# xen_teensy_motherboard_8cv4pt_mki.net
KiCad netlist of a schematic drawn in EAGLE
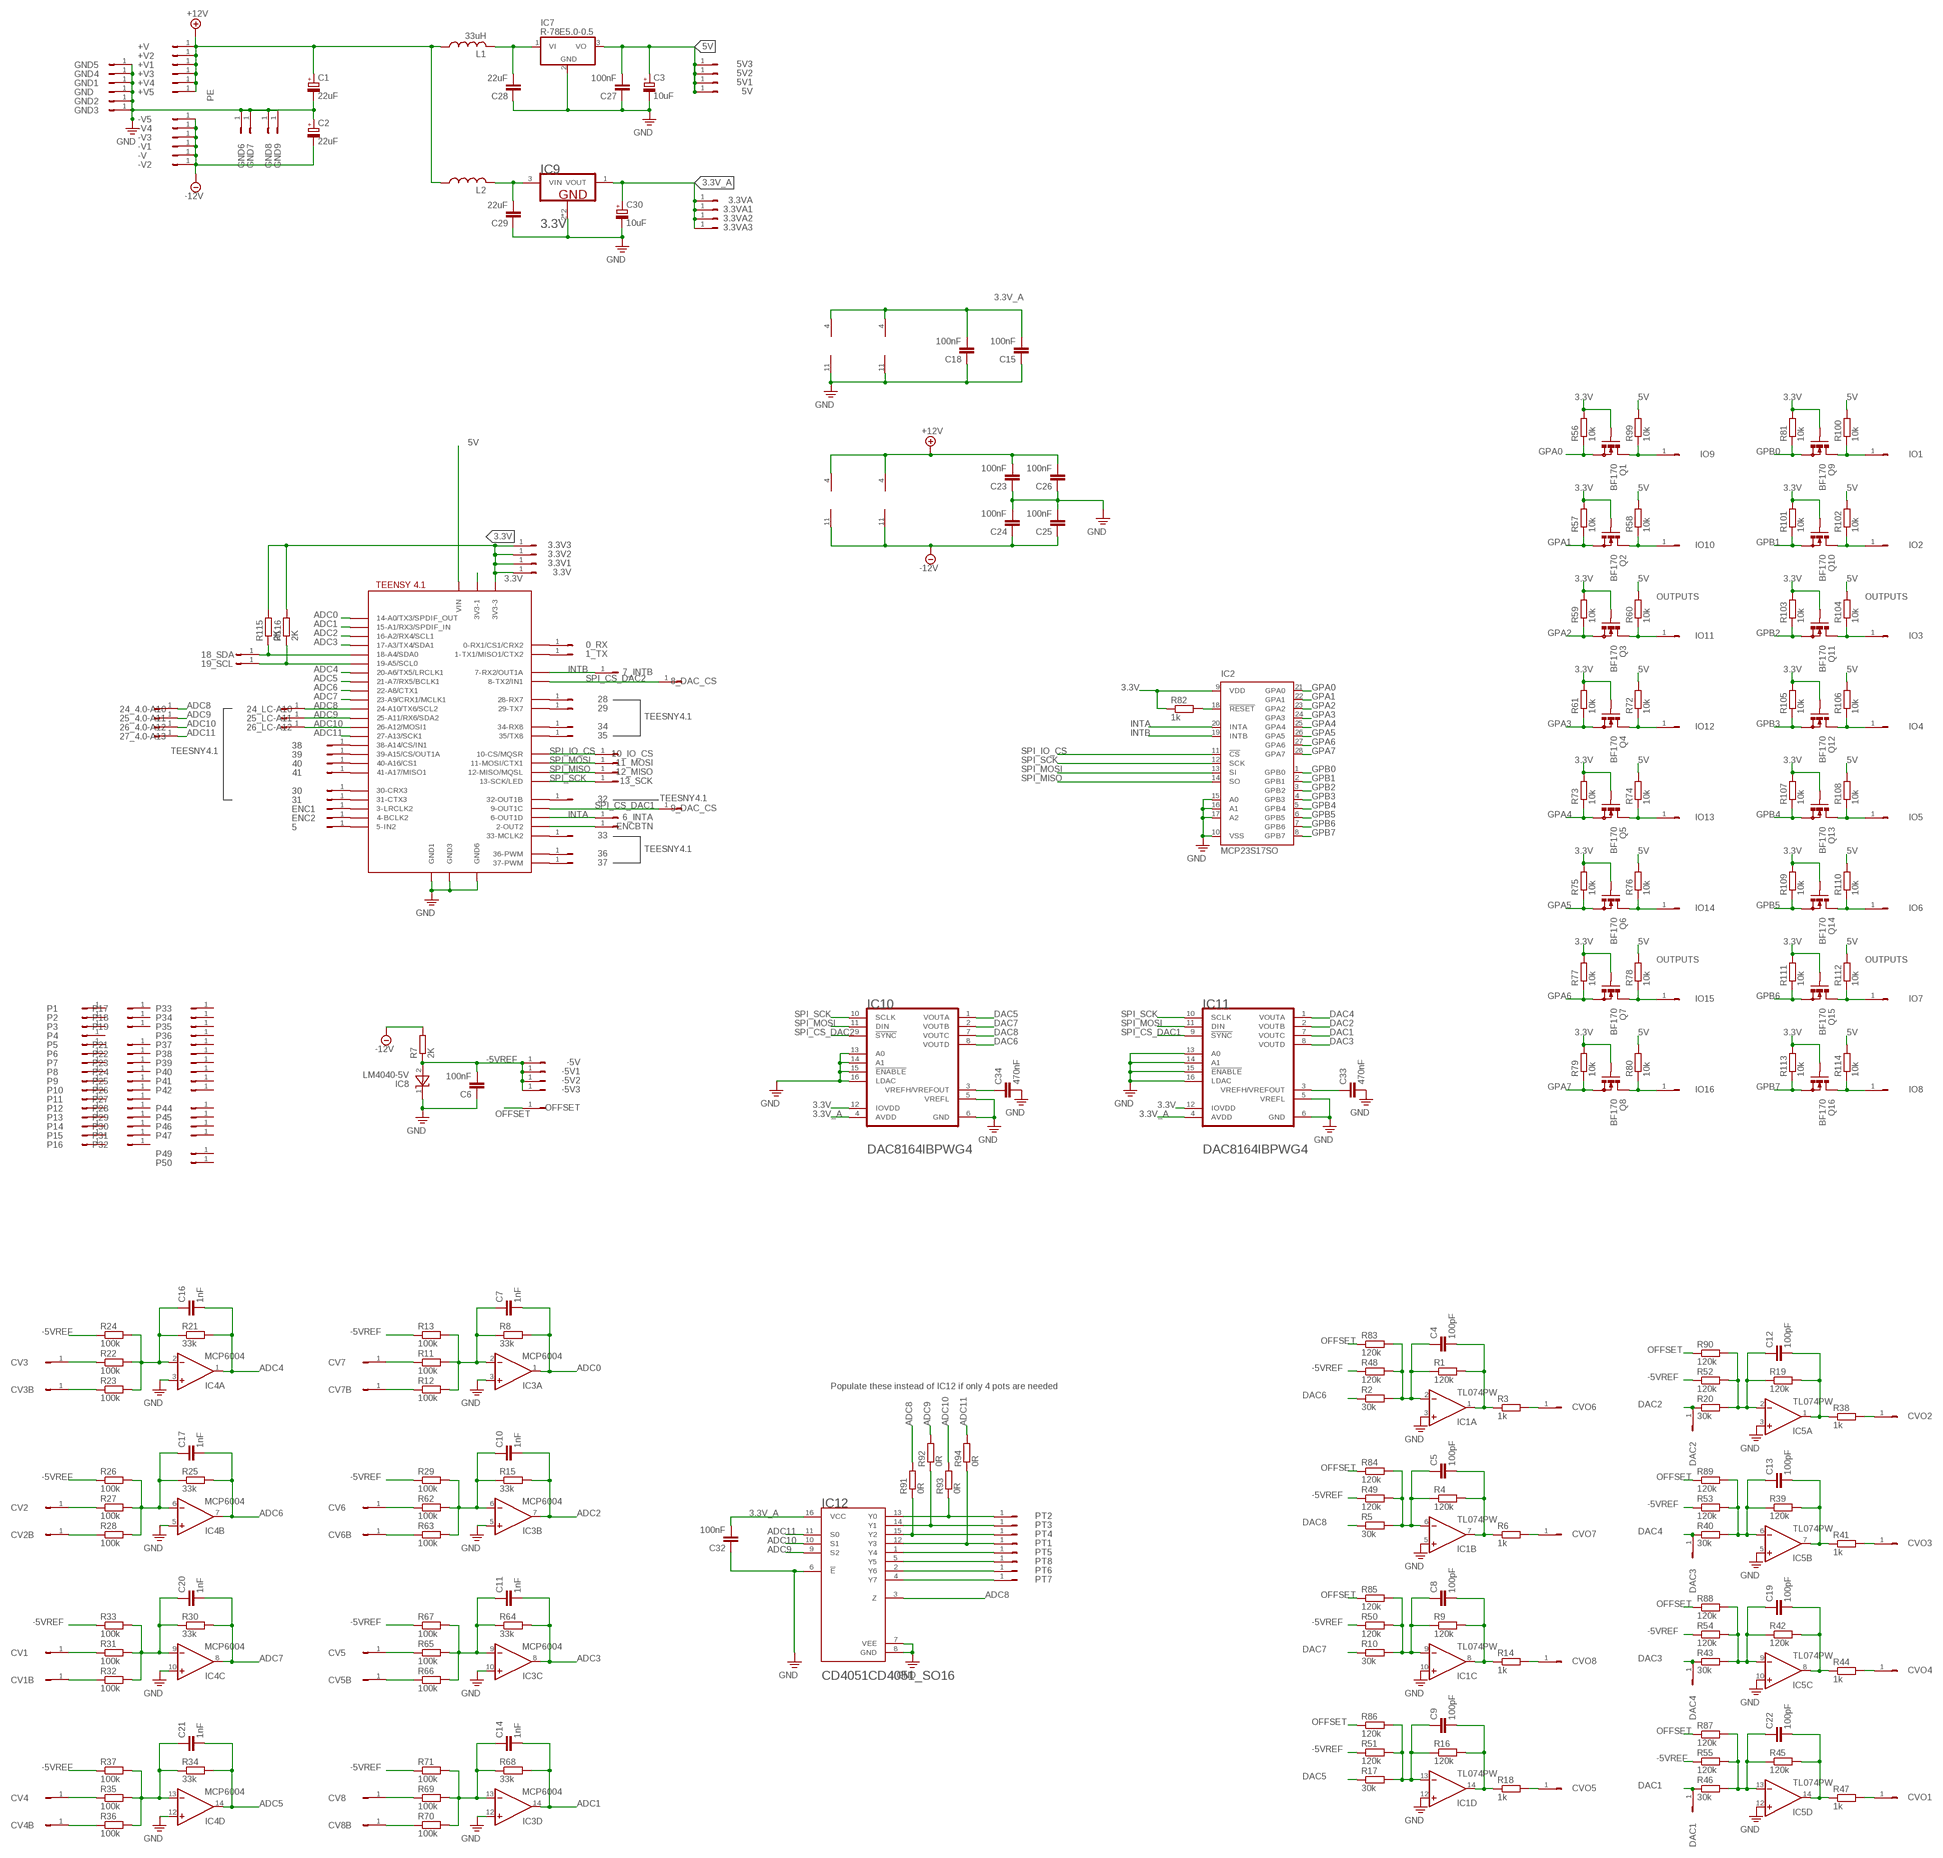
[diagram p0: schematic, sheet 1]

(export (version "E")
  (design (tool "Eeschema 10.0.6"))
  (components
    (comp (ref "+V")
      (value "HEADER/MALE/01")
      (footprint "eagle-import:HEADER_MALE_01")
      (fields (field (name "SPICEPREFIX") "X"))
      (libsource (lib "eagle-import") (part "HEADER/MALE/01"))
    )
    (comp (ref "+V1")
      (value "HEADER/MALE/01")
      (footprint "eagle-import:HEADER_MALE_01")
      (fields (field (name "SPICEPREFIX") "X"))
      (libsource (lib "eagle-import") (part "HEADER/MALE/01"))
    )
    (comp (ref "+V2")
      (value "HEADER/MALE/01")
      (footprint "eagle-import:HEADER_MALE_01")
      (fields (field (name "SPICEPREFIX") "X"))
      (libsource (lib "eagle-import") (part "HEADER/MALE/01"))
    )
    (comp (ref "+V3")
      (value "HEADER/MALE/01")
      (footprint "eagle-import:HEADER_MALE_01")
      (fields (field (name "SPICEPREFIX") "X"))
      (libsource (lib "eagle-import") (part "HEADER/MALE/01"))
    )
    (comp (ref "+V4")
      (value "HEADER/MALE/01")
      (footprint "eagle-import:HEADER_MALE_01")
      (fields (field (name "SPICEPREFIX") "X"))
      (libsource (lib "eagle-import") (part "HEADER/MALE/01"))
    )
    (comp (ref "+V5")
      (value "HEADER/MALE/01")
      (footprint "eagle-import:HEADER_MALE_01")
      (fields (field (name "SPICEPREFIX") "X"))
      (libsource (lib "eagle-import") (part "HEADER/MALE/01"))
    )
    (comp (ref "-5V")
      (value "HEADER/MALE/01")
      (footprint "eagle-import:HEADER_MALE_01")
      (fields (field (name "SPICEPREFIX") "X"))
      (libsource (lib "eagle-import") (part "HEADER/MALE/01"))
    )
    (comp (ref "-5V1")
      (value "HEADER/MALE/01")
      (footprint "eagle-import:HEADER_MALE_01")
      (fields (field (name "SPICEPREFIX") "X"))
      (libsource (lib "eagle-import") (part "HEADER/MALE/01"))
    )
    (comp (ref "-5V2")
      (value "HEADER/MALE/01")
      (footprint "eagle-import:HEADER_MALE_01")
      (fields (field (name "SPICEPREFIX") "X"))
      (libsource (lib "eagle-import") (part "HEADER/MALE/01"))
    )
    (comp (ref "-5V3")
      (value "HEADER/MALE/01")
      (footprint "eagle-import:HEADER_MALE_01")
      (fields (field (name "SPICEPREFIX") "X"))
      (libsource (lib "eagle-import") (part "HEADER/MALE/01"))
    )
    (comp (ref "-V")
      (value "HEADER/MALE/01")
      (footprint "eagle-import:HEADER_MALE_01")
      (fields (field (name "SPICEPREFIX") "X"))
      (libsource (lib "eagle-import") (part "HEADER/MALE/01"))
    )
    (comp (ref "-V1")
      (value "HEADER/MALE/01")
      (footprint "eagle-import:HEADER_MALE_01")
      (fields (field (name "SPICEPREFIX") "X"))
      (libsource (lib "eagle-import") (part "HEADER/MALE/01"))
    )
    (comp (ref "-V2")
      (value "HEADER/MALE/01")
      (footprint "eagle-import:HEADER_MALE_01")
      (fields (field (name "SPICEPREFIX") "X"))
      (libsource (lib "eagle-import") (part "HEADER/MALE/01"))
    )
    (comp (ref "-V3")
      (value "HEADER/MALE/01")
      (footprint "eagle-import:HEADER_MALE_01")
      (fields (field (name "SPICEPREFIX") "X"))
      (libsource (lib "eagle-import") (part "HEADER/MALE/01"))
    )
    (comp (ref "-V4")
      (value "HEADER/MALE/01")
      (footprint "eagle-import:HEADER_MALE_01")
      (fields (field (name "SPICEPREFIX") "X"))
      (libsource (lib "eagle-import") (part "HEADER/MALE/01"))
    )
    (comp (ref "-V5")
      (value "HEADER/MALE/01")
      (footprint "eagle-import:HEADER_MALE_01")
      (fields (field (name "SPICEPREFIX") "X"))
      (libsource (lib "eagle-import") (part "HEADER/MALE/01"))
    )
    (comp (ref "0_RX")
      (value "HEADER/MALE/01")
      (footprint "eagle-import:HEADER_MALE_01")
      (fields (field (name "SPICEPREFIX") "X"))
      (libsource (lib "eagle-import") (part "HEADER/MALE/01"))
    )
    (comp (ref "1_TX")
      (value "HEADER/MALE/01")
      (footprint "eagle-import:HEADER_MALE_01")
      (fields (field (name "SPICEPREFIX") "X"))
      (libsource (lib "eagle-import") (part "HEADER/MALE/01"))
    )
    (comp (ref "3.3V")
      (value "HEADER/MALE/01")
      (footprint "eagle-import:HEADER_MALE_01")
      (fields (field (name "SPICEPREFIX") "X"))
      (libsource (lib "eagle-import") (part "HEADER/MALE/01"))
    )
    (comp (ref "3.3V1")
      (value "HEADER/MALE/01")
      (footprint "eagle-import:HEADER_MALE_01")
      (fields (field (name "SPICEPREFIX") "X"))
      (libsource (lib "eagle-import") (part "HEADER/MALE/01"))
    )
    (comp (ref "3.3V2")
      (value "HEADER/MALE/01")
      (footprint "eagle-import:HEADER_MALE_01")
      (fields (field (name "SPICEPREFIX") "X"))
      (libsource (lib "eagle-import") (part "HEADER/MALE/01"))
    )
    (comp (ref "3.3V3")
      (value "HEADER/MALE/01")
      (footprint "eagle-import:HEADER_MALE_01")
      (fields (field (name "SPICEPREFIX") "X"))
      (libsource (lib "eagle-import") (part "HEADER/MALE/01"))
    )
    (comp (ref "3.3VA")
      (value "HEADER/MALE/01")
      (footprint "eagle-import:HEADER_MALE_01")
      (fields (field (name "SPICEPREFIX") "X"))
      (libsource (lib "eagle-import") (part "HEADER/MALE/01"))
    )
    (comp (ref "3.3VA1")
      (value "HEADER/MALE/01")
      (footprint "eagle-import:HEADER_MALE_01")
      (fields (field (name "SPICEPREFIX") "X"))
      (libsource (lib "eagle-import") (part "HEADER/MALE/01"))
    )
    (comp (ref "3.3VA2")
      (value "HEADER/MALE/01")
      (footprint "eagle-import:HEADER_MALE_01")
      (fields (field (name "SPICEPREFIX") "X"))
      (libsource (lib "eagle-import") (part "HEADER/MALE/01"))
    )
    (comp (ref "3.3VA3")
      (value "HEADER/MALE/01")
      (footprint "eagle-import:HEADER_MALE_01")
      (fields (field (name "SPICEPREFIX") "X"))
      (libsource (lib "eagle-import") (part "HEADER/MALE/01"))
    )
    (comp (ref "5")
      (value "HEADER/MALE/01")
      (footprint "eagle-import:HEADER_MALE_01")
      (fields (field (name "SPICEPREFIX") "X"))
      (libsource (lib "eagle-import") (part "HEADER/MALE/01"))
    )
    (comp (ref "5V")
      (value "HEADER/MALE/01")
      (footprint "eagle-import:HEADER_MALE_01")
      (fields (field (name "SPICEPREFIX") "X"))
      (libsource (lib "eagle-import") (part "HEADER/MALE/01"))
    )
    (comp (ref "5V1")
      (value "HEADER/MALE/01")
      (footprint "eagle-import:HEADER_MALE_01")
      (fields (field (name "SPICEPREFIX") "X"))
      (libsource (lib "eagle-import") (part "HEADER/MALE/01"))
    )
    (comp (ref "5V2")
      (value "HEADER/MALE/01")
      (footprint "eagle-import:HEADER_MALE_01")
      (fields (field (name "SPICEPREFIX") "X"))
      (libsource (lib "eagle-import") (part "HEADER/MALE/01"))
    )
    (comp (ref "5V3")
      (value "HEADER/MALE/01")
      (footprint "eagle-import:HEADER_MALE_01")
      (fields (field (name "SPICEPREFIX") "X"))
      (libsource (lib "eagle-import") (part "HEADER/MALE/01"))
    )
    (comp (ref "6_INTA")
      (value "HEADER/MALE/01")
      (footprint "eagle-import:HEADER_MALE_01")
      (fields (field (name "SPICEPREFIX") "X"))
      (libsource (lib "eagle-import") (part "HEADER/MALE/01"))
    )
    (comp (ref "7_INTB")
      (value "HEADER/MALE/01")
      (footprint "eagle-import:HEADER_MALE_01")
      (fields (field (name "SPICEPREFIX") "X"))
      (libsource (lib "eagle-import") (part "HEADER/MALE/01"))
    )
    (comp (ref "8_DAC_CS")
      (value "HEADER/MALE/01")
      (footprint "eagle-import:HEADER_MALE_01")
      (fields (field (name "SPICEPREFIX") "X"))
      (libsource (lib "eagle-import") (part "HEADER/MALE/01"))
    )
    (comp (ref "9_DAC_CS")
      (value "HEADER/MALE/01")
      (footprint "eagle-import:HEADER_MALE_01")
      (fields (field (name "SPICEPREFIX") "X"))
      (libsource (lib "eagle-import") (part "HEADER/MALE/01"))
    )
    (comp (ref "10_IO_CS")
      (value "HEADER/MALE/01")
      (footprint "eagle-import:HEADER_MALE_01")
      (fields (field (name "SPICEPREFIX") "X"))
      (libsource (lib "eagle-import") (part "HEADER/MALE/01"))
    )
    (comp (ref "11_MOSI")
      (value "HEADER/MALE/01")
      (footprint "eagle-import:HEADER_MALE_01")
      (fields (field (name "SPICEPREFIX") "X"))
      (libsource (lib "eagle-import") (part "HEADER/MALE/01"))
    )
    (comp (ref "12_MISO")
      (value "HEADER/MALE/01")
      (footprint "eagle-import:HEADER_MALE_01")
      (fields (field (name "SPICEPREFIX") "X"))
      (libsource (lib "eagle-import") (part "HEADER/MALE/01"))
    )
    (comp (ref "13_SCK")
      (value "HEADER/MALE/01")
      (footprint "eagle-import:HEADER_MALE_01")
      (fields (field (name "SPICEPREFIX") "X"))
      (libsource (lib "eagle-import") (part "HEADER/MALE/01"))
    )
    (comp (ref "18_SDA")
      (value "HEADER/MALE/01")
      (footprint "eagle-import:HEADER_MALE_01")
      (fields (field (name "SPICEPREFIX") "X"))
      (libsource (lib "eagle-import") (part "HEADER/MALE/01"))
    )
    (comp (ref "19_SCL")
      (value "HEADER/MALE/01")
      (footprint "eagle-import:HEADER_MALE_01")
      (fields (field (name "SPICEPREFIX") "X"))
      (libsource (lib "eagle-import") (part "HEADER/MALE/01"))
    )
    (comp (ref "24_4.0-A10")
      (value "HEADER/MALE/01")
      (footprint "eagle-import:HEADER_MALE_01")
      (fields (field (name "SPICEPREFIX") "X"))
      (libsource (lib "eagle-import") (part "HEADER/MALE/01"))
    )
    (comp (ref "24_LC-A10")
      (value "HEADER/MALE/01")
      (footprint "eagle-import:HEADER_MALE_01")
      (fields (field (name "SPICEPREFIX") "X"))
      (libsource (lib "eagle-import") (part "HEADER/MALE/01"))
    )
    (comp (ref "25_4.0-A11")
      (value "HEADER/MALE/01")
      (footprint "eagle-import:HEADER_MALE_01")
      (fields (field (name "SPICEPREFIX") "X"))
      (libsource (lib "eagle-import") (part "HEADER/MALE/01"))
    )
    (comp (ref "25_LC-A11")
      (value "HEADER/MALE/01")
      (footprint "eagle-import:HEADER_MALE_01")
      (fields (field (name "SPICEPREFIX") "X"))
      (libsource (lib "eagle-import") (part "HEADER/MALE/01"))
    )
    (comp (ref "26_4.0-A12")
      (value "HEADER/MALE/01")
      (footprint "eagle-import:HEADER_MALE_01")
      (fields (field (name "SPICEPREFIX") "X"))
      (libsource (lib "eagle-import") (part "HEADER/MALE/01"))
    )
    (comp (ref "26_LC-A12")
      (value "HEADER/MALE/01")
      (footprint "eagle-import:HEADER_MALE_01")
      (fields (field (name "SPICEPREFIX") "X"))
      (libsource (lib "eagle-import") (part "HEADER/MALE/01"))
    )
    (comp (ref "27_4.0-A13")
      (value "HEADER/MALE/01")
      (footprint "eagle-import:HEADER_MALE_01")
      (fields (field (name "SPICEPREFIX") "X"))
      (libsource (lib "eagle-import") (part "HEADER/MALE/01"))
    )
    (comp (ref "28")
      (value "HEADER/MALE/01")
      (footprint "eagle-import:HEADER_MALE_01")
      (fields (field (name "SPICEPREFIX") "X"))
      (libsource (lib "eagle-import") (part "HEADER/MALE/01"))
    )
    (comp (ref "29")
      (value "HEADER/MALE/01")
      (footprint "eagle-import:HEADER_MALE_01")
      (fields (field (name "SPICEPREFIX") "X"))
      (libsource (lib "eagle-import") (part "HEADER/MALE/01"))
    )
    (comp (ref "30")
      (value "HEADER/MALE/01")
      (footprint "eagle-import:HEADER_MALE_01")
      (fields (field (name "SPICEPREFIX") "X"))
      (libsource (lib "eagle-import") (part "HEADER/MALE/01"))
    )
    (comp (ref "31")
      (value "HEADER/MALE/01")
      (footprint "eagle-import:HEADER_MALE_01")
      (fields (field (name "SPICEPREFIX") "X"))
      (libsource (lib "eagle-import") (part "HEADER/MALE/01"))
    )
    (comp (ref "32")
      (value "HEADER/MALE/01")
      (footprint "eagle-import:HEADER_MALE_01")
      (fields (field (name "SPICEPREFIX") "X"))
      (libsource (lib "eagle-import") (part "HEADER/MALE/01"))
    )
    (comp (ref "33")
      (value "HEADER/MALE/01")
      (footprint "eagle-import:HEADER_MALE_01")
      (fields (field (name "SPICEPREFIX") "X"))
      (libsource (lib "eagle-import") (part "HEADER/MALE/01"))
    )
    (comp (ref "34")
      (value "HEADER/MALE/01")
      (footprint "eagle-import:HEADER_MALE_01")
      (fields (field (name "SPICEPREFIX") "X"))
      (libsource (lib "eagle-import") (part "HEADER/MALE/01"))
    )
    (comp (ref "35")
      (value "HEADER/MALE/01")
      (footprint "eagle-import:HEADER_MALE_01")
      (fields (field (name "SPICEPREFIX") "X"))
      (libsource (lib "eagle-import") (part "HEADER/MALE/01"))
    )
    (comp (ref "36")
      (value "HEADER/MALE/01")
      (footprint "eagle-import:HEADER_MALE_01")
      (fields (field (name "SPICEPREFIX") "X"))
      (libsource (lib "eagle-import") (part "HEADER/MALE/01"))
    )
    (comp (ref "37")
      (value "HEADER/MALE/01")
      (footprint "eagle-import:HEADER_MALE_01")
      (fields (field (name "SPICEPREFIX") "X"))
      (libsource (lib "eagle-import") (part "HEADER/MALE/01"))
    )
    (comp (ref "38")
      (value "HEADER/MALE/01")
      (footprint "eagle-import:HEADER_MALE_01")
      (fields (field (name "SPICEPREFIX") "X"))
      (libsource (lib "eagle-import") (part "HEADER/MALE/01"))
    )
    (comp (ref "39")
      (value "HEADER/MALE/01")
      (footprint "eagle-import:HEADER_MALE_01")
      (fields (field (name "SPICEPREFIX") "X"))
      (libsource (lib "eagle-import") (part "HEADER/MALE/01"))
    )
    (comp (ref "40")
      (value "HEADER/MALE/01")
      (footprint "eagle-import:HEADER_MALE_01")
      (fields (field (name "SPICEPREFIX") "X"))
      (libsource (lib "eagle-import") (part "HEADER/MALE/01"))
    )
    (comp (ref "41")
      (value "HEADER/MALE/01")
      (footprint "eagle-import:HEADER_MALE_01")
      (fields (field (name "SPICEPREFIX") "X"))
      (libsource (lib "eagle-import") (part "HEADER/MALE/01"))
    )
    (comp (ref "C1")
      (value "22uF")
      (footprint "eagle-import:SV-C")
      (fields (field (name "SPICEPREFIX") "C"))
      (libsource (lib "eagle-import") (part "CAPACITOR/POLARIZEDSMDC"))
    )
    (comp (ref "C2")
      (value "22uF")
      (footprint "eagle-import:SV-C")
      (fields (field (name "SPICEPREFIX") "C"))
      (libsource (lib "eagle-import") (part "CAPACITOR/POLARIZEDSMDC"))
    )
    (comp (ref "C3")
      (value "10uF")
      (footprint "eagle-import:SV-B")
      (fields (field (name "SPICEPREFIX") "C"))
      (libsource (lib "eagle-import") (part "CAPACITOR/POLARIZEDSMDB"))
    )
    (comp (ref "C4")
      (value "100pF")
      (footprint "eagle-import:C0603")
      (libsource (lib "eagle-import") (part "CAPACITORC0603"))
    )
    (comp (ref "C5")
      (value "100pF")
      (footprint "eagle-import:C0603")
      (libsource (lib "eagle-import") (part "CAPACITORC0603"))
    )
    (comp (ref "C6")
      (value "100nF")
      (footprint "eagle-import:C0603")
      (libsource (lib "eagle-import") (part "CAPACITORC0603"))
    )
    (comp (ref "C7")
      (value "1nF")
      (footprint "eagle-import:C0603")
      (libsource (lib "eagle-import") (part "CAPACITORC0603"))
    )
    (comp (ref "C8")
      (value "100pF")
      (footprint "eagle-import:C0603")
      (libsource (lib "eagle-import") (part "CAPACITORC0603"))
    )
    (comp (ref "C9")
      (value "100pF")
      (footprint "eagle-import:C0603")
      (libsource (lib "eagle-import") (part "CAPACITORC0603"))
    )
    (comp (ref "C10")
      (value "1nF")
      (footprint "eagle-import:C0603")
      (libsource (lib "eagle-import") (part "CAPACITORC0603"))
    )
    (comp (ref "C11")
      (value "1nF")
      (footprint "eagle-import:C0603")
      (libsource (lib "eagle-import") (part "CAPACITORC0603"))
    )
    (comp (ref "C12")
      (value "100pF")
      (footprint "eagle-import:C0603")
      (libsource (lib "eagle-import") (part "CAPACITORC0603"))
    )
    (comp (ref "C13")
      (value "100pF")
      (footprint "eagle-import:C0603")
      (libsource (lib "eagle-import") (part "CAPACITORC0603"))
    )
    (comp (ref "C14")
      (value "1nF")
      (footprint "eagle-import:C0603")
      (libsource (lib "eagle-import") (part "CAPACITORC0603"))
    )
    (comp (ref "C15")
      (value "100nF")
      (footprint "eagle-import:C0603")
      (libsource (lib "eagle-import") (part "CAPACITORC0603"))
    )
    (comp (ref "C16")
      (value "1nF")
      (footprint "eagle-import:C0603")
      (libsource (lib "eagle-import") (part "CAPACITORC0603"))
    )
    (comp (ref "C17")
      (value "1nF")
      (footprint "eagle-import:C0603")
      (libsource (lib "eagle-import") (part "CAPACITORC0603"))
    )
    (comp (ref "C18")
      (value "100nF")
      (footprint "eagle-import:C0603")
      (libsource (lib "eagle-import") (part "CAPACITORC0603"))
    )
    (comp (ref "C19")
      (value "100pF")
      (footprint "eagle-import:C0603")
      (libsource (lib "eagle-import") (part "CAPACITORC0603"))
    )
    (comp (ref "C20")
      (value "1nF")
      (footprint "eagle-import:C0603")
      (libsource (lib "eagle-import") (part "CAPACITORC0603"))
    )
    (comp (ref "C21")
      (value "1nF")
      (footprint "eagle-import:C0603")
      (libsource (lib "eagle-import") (part "CAPACITORC0603"))
    )
    (comp (ref "C22")
      (value "100pF")
      (footprint "eagle-import:C0603")
      (libsource (lib "eagle-import") (part "CAPACITORC0603"))
    )
    (comp (ref "C23")
      (value "100nF")
      (footprint "eagle-import:C0603")
      (libsource (lib "eagle-import") (part "CAPACITORC0603"))
    )
    (comp (ref "C24")
      (value "100nF")
      (footprint "eagle-import:C0603")
      (libsource (lib "eagle-import") (part "CAPACITORC0603"))
    )
    (comp (ref "C25")
      (value "100nF")
      (footprint "eagle-import:C0603")
      (libsource (lib "eagle-import") (part "CAPACITORC0603"))
    )
    (comp (ref "C26")
      (value "100nF")
      (footprint "eagle-import:C0603")
      (libsource (lib "eagle-import") (part "CAPACITORC0603"))
    )
    (comp (ref "C27")
      (value "100nF")
      (footprint "eagle-import:C0603")
      (libsource (lib "eagle-import") (part "CAPACITORC0603"))
    )
    (comp (ref "C28")
      (value "22uF")
      (footprint "eagle-import:C0805")
      (libsource (lib "eagle-import") (part "CAPACITORC0805"))
    )
    (comp (ref "C29")
      (value "22uF")
      (footprint "eagle-import:C0805")
      (libsource (lib "eagle-import") (part "CAPACITORC0805"))
    )
    (comp (ref "C30")
      (value "10uF")
      (footprint "eagle-import:SV-B")
      (fields (field (name "SPICEPREFIX") "C"))
      (libsource (lib "eagle-import") (part "CAPACITOR/POLARIZEDSMDB"))
    )
    (comp (ref "C32")
      (value "100nF")
      (footprint "eagle-import:C0603")
      (libsource (lib "eagle-import") (part "CAPACITORC0603"))
    )
    (comp (ref "C33")
      (value "470nF")
      (footprint "eagle-import:C0603")
      (libsource (lib "eagle-import") (part "CAPACITORC0603"))
    )
    (comp (ref "C34")
      (value "470nF")
      (footprint "eagle-import:C0603")
      (libsource (lib "eagle-import") (part "CAPACITORC0603"))
    )
    (comp (ref "CV1")
      (value "HEADER/MALE/01")
      (footprint "eagle-import:HEADER_MALE_01")
      (fields (field (name "SPICEPREFIX") "X"))
      (libsource (lib "eagle-import") (part "HEADER/MALE/01"))
    )
    (comp (ref "CV1B")
      (value "HEADER/MALE/01")
      (footprint "eagle-import:HEADER_MALE_01")
      (fields (field (name "SPICEPREFIX") "X"))
      (libsource (lib "eagle-import") (part "HEADER/MALE/01"))
    )
    (comp (ref "CV2")
      (value "HEADER/MALE/01")
      (footprint "eagle-import:HEADER_MALE_01")
      (fields (field (name "SPICEPREFIX") "X"))
      (libsource (lib "eagle-import") (part "HEADER/MALE/01"))
    )
    (comp (ref "CV2B")
      (value "HEADER/MALE/01")
      (footprint "eagle-import:HEADER_MALE_01")
      (fields (field (name "SPICEPREFIX") "X"))
      (libsource (lib "eagle-import") (part "HEADER/MALE/01"))
    )
    (comp (ref "CV3")
      (value "HEADER/MALE/01")
      (footprint "eagle-import:HEADER_MALE_01")
      (fields (field (name "SPICEPREFIX") "X"))
      (libsource (lib "eagle-import") (part "HEADER/MALE/01"))
    )
    (comp (ref "CV3B")
      (value "HEADER/MALE/01")
      (footprint "eagle-import:HEADER_MALE_01")
      (fields (field (name "SPICEPREFIX") "X"))
      (libsource (lib "eagle-import") (part "HEADER/MALE/01"))
    )
    (comp (ref "CV4")
      (value "HEADER/MALE/01")
      (footprint "eagle-import:HEADER_MALE_01")
      (fields (field (name "SPICEPREFIX") "X"))
      (libsource (lib "eagle-import") (part "HEADER/MALE/01"))
    )
    (comp (ref "CV4B")
      (value "HEADER/MALE/01")
      (footprint "eagle-import:HEADER_MALE_01")
      (fields (field (name "SPICEPREFIX") "X"))
      (libsource (lib "eagle-import") (part "HEADER/MALE/01"))
    )
    (comp (ref "CV5")
      (value "HEADER/MALE/01")
      (footprint "eagle-import:HEADER_MALE_01")
      (fields (field (name "SPICEPREFIX") "X"))
      (libsource (lib "eagle-import") (part "HEADER/MALE/01"))
    )
    (comp (ref "CV5B")
      (value "HEADER/MALE/01")
      (footprint "eagle-import:HEADER_MALE_01")
      (fields (field (name "SPICEPREFIX") "X"))
      (libsource (lib "eagle-import") (part "HEADER/MALE/01"))
    )
    (comp (ref "CV6")
      (value "HEADER/MALE/01")
      (footprint "eagle-import:HEADER_MALE_01")
      (fields (field (name "SPICEPREFIX") "X"))
      (libsource (lib "eagle-import") (part "HEADER/MALE/01"))
    )
    (comp (ref "CV6B")
      (value "HEADER/MALE/01")
      (footprint "eagle-import:HEADER_MALE_01")
      (fields (field (name "SPICEPREFIX") "X"))
      (libsource (lib "eagle-import") (part "HEADER/MALE/01"))
    )
    (comp (ref "CV7")
      (value "HEADER/MALE/01")
      (footprint "eagle-import:HEADER_MALE_01")
      (fields (field (name "SPICEPREFIX") "X"))
      (libsource (lib "eagle-import") (part "HEADER/MALE/01"))
    )
    (comp (ref "CV7B")
      (value "HEADER/MALE/01")
      (footprint "eagle-import:HEADER_MALE_01")
      (fields (field (name "SPICEPREFIX") "X"))
      (libsource (lib "eagle-import") (part "HEADER/MALE/01"))
    )
    (comp (ref "CV8")
      (value "HEADER/MALE/01")
      (footprint "eagle-import:HEADER_MALE_01")
      (fields (field (name "SPICEPREFIX") "X"))
      (libsource (lib "eagle-import") (part "HEADER/MALE/01"))
    )
    (comp (ref "CV8B")
      (value "HEADER/MALE/01")
      (footprint "eagle-import:HEADER_MALE_01")
      (fields (field (name "SPICEPREFIX") "X"))
      (libsource (lib "eagle-import") (part "HEADER/MALE/01"))
    )
    (comp (ref "CVO1")
      (value "HEADER/MALE/01")
      (footprint "eagle-import:HEADER_MALE_01")
      (fields (field (name "SPICEPREFIX") "X"))
      (libsource (lib "eagle-import") (part "HEADER/MALE/01"))
    )
    (comp (ref "CVO2")
      (value "HEADER/MALE/01")
      (footprint "eagle-import:HEADER_MALE_01")
      (fields (field (name "SPICEPREFIX") "X"))
      (libsource (lib "eagle-import") (part "HEADER/MALE/01"))
    )
    (comp (ref "CVO3")
      (value "HEADER/MALE/01")
      (footprint "eagle-import:HEADER_MALE_01")
      (fields (field (name "SPICEPREFIX") "X"))
      (libsource (lib "eagle-import") (part "HEADER/MALE/01"))
    )
    (comp (ref "CVO4")
      (value "HEADER/MALE/01")
      (footprint "eagle-import:HEADER_MALE_01")
      (fields (field (name "SPICEPREFIX") "X"))
      (libsource (lib "eagle-import") (part "HEADER/MALE/01"))
    )
    (comp (ref "CVO5")
      (value "HEADER/MALE/01")
      (footprint "eagle-import:HEADER_MALE_01")
      (fields (field (name "SPICEPREFIX") "X"))
      (libsource (lib "eagle-import") (part "HEADER/MALE/01"))
    )
    (comp (ref "CVO6")
      (value "HEADER/MALE/01")
      (footprint "eagle-import:HEADER_MALE_01")
      (fields (field (name "SPICEPREFIX") "X"))
      (libsource (lib "eagle-import") (part "HEADER/MALE/01"))
    )
    (comp (ref "CVO7")
      (value "HEADER/MALE/01")
      (footprint "eagle-import:HEADER_MALE_01")
      (fields (field (name "SPICEPREFIX") "X"))
      (libsource (lib "eagle-import") (part "HEADER/MALE/01"))
    )
    (comp (ref "CVO8")
      (value "HEADER/MALE/01")
      (footprint "eagle-import:HEADER_MALE_01")
      (fields (field (name "SPICEPREFIX") "X"))
      (libsource (lib "eagle-import") (part "HEADER/MALE/01"))
    )
    (comp (ref "DAC1")
      (value "HEADER/MALE/01")
      (footprint "eagle-import:HEADER_MALE_01")
      (fields (field (name "SPICEPREFIX") "X"))
      (libsource (lib "eagle-import") (part "HEADER/MALE/01"))
    )
    (comp (ref "DAC2")
      (value "HEADER/MALE/01")
      (footprint "eagle-import:HEADER_MALE_01")
      (fields (field (name "SPICEPREFIX") "X"))
      (libsource (lib "eagle-import") (part "HEADER/MALE/01"))
    )
    (comp (ref "DAC3")
      (value "HEADER/MALE/01")
      (footprint "eagle-import:HEADER_MALE_01")
      (fields (field (name "SPICEPREFIX") "X"))
      (libsource (lib "eagle-import") (part "HEADER/MALE/01"))
    )
    (comp (ref "DAC4")
      (value "HEADER/MALE/01")
      (footprint "eagle-import:HEADER_MALE_01")
      (fields (field (name "SPICEPREFIX") "X"))
      (libsource (lib "eagle-import") (part "HEADER/MALE/01"))
    )
    (comp (ref "ENC1")
      (value "HEADER/MALE/01")
      (footprint "eagle-import:HEADER_MALE_01")
      (fields (field (name "SPICEPREFIX") "X"))
      (libsource (lib "eagle-import") (part "HEADER/MALE/01"))
    )
    (comp (ref "ENC2")
      (value "HEADER/MALE/01")
      (footprint "eagle-import:HEADER_MALE_01")
      (fields (field (name "SPICEPREFIX") "X"))
      (libsource (lib "eagle-import") (part "HEADER/MALE/01"))
    )
    (comp (ref "ENCBTN")
      (value "HEADER/MALE/01")
      (footprint "eagle-import:HEADER_MALE_01")
      (fields (field (name "SPICEPREFIX") "X"))
      (libsource (lib "eagle-import") (part "HEADER/MALE/01"))
    )
    (comp (ref "GND")
      (value "HEADER/MALE/01")
      (footprint "eagle-import:HEADER_MALE_01")
      (fields (field (name "SPICEPREFIX") "X"))
      (libsource (lib "eagle-import") (part "HEADER/MALE/01"))
    )
    (comp (ref "GND1")
      (value "HEADER/MALE/01")
      (footprint "eagle-import:HEADER_MALE_01")
      (fields (field (name "SPICEPREFIX") "X"))
      (libsource (lib "eagle-import") (part "HEADER/MALE/01"))
    )
    (comp (ref "GND2")
      (value "HEADER/MALE/01")
      (footprint "eagle-import:HEADER_MALE_01")
      (fields (field (name "SPICEPREFIX") "X"))
      (libsource (lib "eagle-import") (part "HEADER/MALE/01"))
    )
    (comp (ref "GND3")
      (value "HEADER/MALE/01")
      (footprint "eagle-import:HEADER_MALE_01")
      (fields (field (name "SPICEPREFIX") "X"))
      (libsource (lib "eagle-import") (part "HEADER/MALE/01"))
    )
    (comp (ref "GND4")
      (value "HEADER/MALE/01")
      (footprint "eagle-import:HEADER_MALE_01")
      (fields (field (name "SPICEPREFIX") "X"))
      (libsource (lib "eagle-import") (part "HEADER/MALE/01"))
    )
    (comp (ref "GND5")
      (value "HEADER/MALE/01")
      (footprint "eagle-import:HEADER_MALE_01")
      (fields (field (name "SPICEPREFIX") "X"))
      (libsource (lib "eagle-import") (part "HEADER/MALE/01"))
    )
    (comp (ref "GND6")
      (value "HEADER/MALE/01")
      (footprint "eagle-import:HEADER_MALE_01")
      (fields (field (name "SPICEPREFIX") "X"))
      (libsource (lib "eagle-import") (part "HEADER/MALE/01"))
    )
    (comp (ref "GND7")
      (value "HEADER/MALE/01")
      (footprint "eagle-import:HEADER_MALE_01")
      (fields (field (name "SPICEPREFIX") "X"))
      (libsource (lib "eagle-import") (part "HEADER/MALE/01"))
    )
    (comp (ref "GND8")
      (value "HEADER/MALE/01")
      (footprint "eagle-import:HEADER_MALE_01")
      (fields (field (name "SPICEPREFIX") "X"))
      (libsource (lib "eagle-import") (part "HEADER/MALE/01"))
    )
    (comp (ref "GND9")
      (value "HEADER/MALE/01")
      (footprint "eagle-import:HEADER_MALE_01")
      (fields (field (name "SPICEPREFIX") "X"))
      (libsource (lib "eagle-import") (part "HEADER/MALE/01"))
    )
    (comp (ref "IC1")
      (value "TL074PW")
      (footprint "eagle-import:TSSOP14")
      (libsource (lib "eagle-import") (part "TL074PW"))
    )
    (comp (ref "IC2")
      (value "MCP23S17SO")
      (footprint "eagle-import:SO28W")
      (fields (field (name "MF") "MICROCHIP") (field (name "MPN") "MCP23S17-E/SO"))
      (libsource (lib "eagle-import") (part "MCP23S17SO"))
    )
    (comp (ref "IC3")
      (value "MCP6004")
      (footprint "eagle-import:TSSOP14")
      (libsource (lib "eagle-import") (part "TL074PW"))
    )
    (comp (ref "IC4")
      (value "MCP6004")
      (footprint "eagle-import:TSSOP14")
      (libsource (lib "eagle-import") (part "TL074PW"))
    )
    (comp (ref "IC5")
      (value "TL074PW")
      (footprint "eagle-import:TSSOP14")
      (libsource (lib "eagle-import") (part "TL074PW"))
    )
    (comp (ref "IC6")
      (value "TEENSY41-OUTER")
      (footprint "eagle-import:TENNSY41-OUTER")
      (libsource (lib "eagle-import") (part "TEENSY41-OUTER"))
    )
    (comp (ref "IC7")
      (value "R-78E5.0-0.5")
      (footprint "eagle-import:WE78")
      (libsource (lib "eagle-import") (part "WE173950378"))
    )
    (comp (ref "IC8")
      (value "LM4040-5V")
      (footprint "eagle-import:SOT-23")
      (libsource (lib "eagle-import") (part "LM4040CYM3-2.5"))
    )
    (comp (ref "IC9")
      (value "3.3V")
      (footprint "eagle-import:LD2981-SOT89")
      (fields (field (name "MF") "STMicroelectronics") (field (name "MPN") "LD2981CU33TR"))
      (libsource (lib "eagle-import") (part "LD2981LD2981-SOT89"))
    )
    (comp (ref "IC10")
      (value "DAC8164")
      (footprint "eagle-import:TEXAS_INSTRUMENTS_DAC8164IBPWG4_1")
      (fields (field (name "MF") "Texas Instruments") (field (name "MPN") "DAC8164IBPWG4"))
      (libsource (lib "eagle-import") (part "TEXAS_INSTRUMENTS_DAC8164IBPWG4TEXAS_INSTRUMENTS_DAC8164IBPWG4_0_1"))
    )
    (comp (ref "IC11")
      (value "DAC8164")
      (footprint "eagle-import:TEXAS_INSTRUMENTS_DAC8164IBPWG4_1")
      (fields (field (name "MF") "Texas Instruments") (field (name "MPN") "DAC8164IBPWG4"))
      (libsource (lib "eagle-import") (part "TEXAS_INSTRUMENTS_DAC8164IBPWG4TEXAS_INSTRUMENTS_DAC8164IBPWG4_0_1"))
    )
    (comp (ref "IC12")
      (value "CD4051CD4051_SO16")
      (footprint "eagle-import:SO16")
      (libsource (lib "eagle-import") (part "CD4051CD4051_SO16"))
    )
    (comp (ref "IO1")
      (value "HEADER/MALE/01")
      (footprint "eagle-import:HEADER_MALE_01")
      (fields (field (name "SPICEPREFIX") "X"))
      (libsource (lib "eagle-import") (part "HEADER/MALE/01"))
    )
    (comp (ref "IO2")
      (value "HEADER/MALE/01")
      (footprint "eagle-import:HEADER_MALE_01")
      (fields (field (name "SPICEPREFIX") "X"))
      (libsource (lib "eagle-import") (part "HEADER/MALE/01"))
    )
    (comp (ref "IO3")
      (value "HEADER/MALE/01")
      (footprint "eagle-import:HEADER_MALE_01")
      (fields (field (name "SPICEPREFIX") "X"))
      (libsource (lib "eagle-import") (part "HEADER/MALE/01"))
    )
    (comp (ref "IO4")
      (value "HEADER/MALE/01")
      (footprint "eagle-import:HEADER_MALE_01")
      (fields (field (name "SPICEPREFIX") "X"))
      (libsource (lib "eagle-import") (part "HEADER/MALE/01"))
    )
    (comp (ref "IO5")
      (value "HEADER/MALE/01")
      (footprint "eagle-import:HEADER_MALE_01")
      (fields (field (name "SPICEPREFIX") "X"))
      (libsource (lib "eagle-import") (part "HEADER/MALE/01"))
    )
    (comp (ref "IO6")
      (value "HEADER/MALE/01")
      (footprint "eagle-import:HEADER_MALE_01")
      (fields (field (name "SPICEPREFIX") "X"))
      (libsource (lib "eagle-import") (part "HEADER/MALE/01"))
    )
    (comp (ref "IO7")
      (value "HEADER/MALE/01")
      (footprint "eagle-import:HEADER_MALE_01")
      (fields (field (name "SPICEPREFIX") "X"))
      (libsource (lib "eagle-import") (part "HEADER/MALE/01"))
    )
    (comp (ref "IO8")
      (value "HEADER/MALE/01")
      (footprint "eagle-import:HEADER_MALE_01")
      (fields (field (name "SPICEPREFIX") "X"))
      (libsource (lib "eagle-import") (part "HEADER/MALE/01"))
    )
    (comp (ref "IO9")
      (value "HEADER/MALE/01")
      (footprint "eagle-import:HEADER_MALE_01")
      (fields (field (name "SPICEPREFIX") "X"))
      (libsource (lib "eagle-import") (part "HEADER/MALE/01"))
    )
    (comp (ref "IO10")
      (value "HEADER/MALE/01")
      (footprint "eagle-import:HEADER_MALE_01")
      (fields (field (name "SPICEPREFIX") "X"))
      (libsource (lib "eagle-import") (part "HEADER/MALE/01"))
    )
    (comp (ref "IO11")
      (value "HEADER/MALE/01")
      (footprint "eagle-import:HEADER_MALE_01")
      (fields (field (name "SPICEPREFIX") "X"))
      (libsource (lib "eagle-import") (part "HEADER/MALE/01"))
    )
    (comp (ref "IO12")
      (value "HEADER/MALE/01")
      (footprint "eagle-import:HEADER_MALE_01")
      (fields (field (name "SPICEPREFIX") "X"))
      (libsource (lib "eagle-import") (part "HEADER/MALE/01"))
    )
    (comp (ref "IO13")
      (value "HEADER/MALE/01")
      (footprint "eagle-import:HEADER_MALE_01")
      (fields (field (name "SPICEPREFIX") "X"))
      (libsource (lib "eagle-import") (part "HEADER/MALE/01"))
    )
    (comp (ref "IO14")
      (value "HEADER/MALE/01")
      (footprint "eagle-import:HEADER_MALE_01")
      (fields (field (name "SPICEPREFIX") "X"))
      (libsource (lib "eagle-import") (part "HEADER/MALE/01"))
    )
    (comp (ref "IO15")
      (value "HEADER/MALE/01")
      (footprint "eagle-import:HEADER_MALE_01")
      (fields (field (name "SPICEPREFIX") "X"))
      (libsource (lib "eagle-import") (part "HEADER/MALE/01"))
    )
    (comp (ref "IO16")
      (value "HEADER/MALE/01")
      (footprint "eagle-import:HEADER_MALE_01")
      (fields (field (name "SPICEPREFIX") "X"))
      (libsource (lib "eagle-import") (part "HEADER/MALE/01"))
    )
    (comp (ref "L1")
      (value "33uH")
      (footprint "eagle-import:L2012C")
      (libsource (lib "eagle-import") (part "INDUCTORL2012C"))
    )
    (comp (ref "L2")
      (value "INDUCTORL0603")
      (footprint "eagle-import:R0603")
      (libsource (lib "eagle-import") (part "INDUCTORL0603"))
    )
    (comp (ref "OFFSET")
      (value "HEADER/MALE/01")
      (footprint "eagle-import:HEADER_MALE_01")
      (fields (field (name "SPICEPREFIX") "X"))
      (libsource (lib "eagle-import") (part "HEADER/MALE/01"))
    )
    (comp (ref "P1")
      (value "HEADER/MALE/01NOBORDER")
      (footprint "eagle-import:HEADER_MALE_01_NOBORDER")
      (fields (field (name "SPICEPREFIX") "X"))
      (libsource (lib "eagle-import") (part "HEADER/MALE/01NOBORDER"))
    )
    (comp (ref "P2")
      (value "HEADER/MALE/01NOBORDER")
      (footprint "eagle-import:HEADER_MALE_01_NOBORDER")
      (fields (field (name "SPICEPREFIX") "X"))
      (libsource (lib "eagle-import") (part "HEADER/MALE/01NOBORDER"))
    )
    (comp (ref "P3")
      (value "HEADER/MALE/01NOBORDER")
      (footprint "eagle-import:HEADER_MALE_01_NOBORDER")
      (fields (field (name "SPICEPREFIX") "X"))
      (libsource (lib "eagle-import") (part "HEADER/MALE/01NOBORDER"))
    )
    (comp (ref "P4")
      (value "HEADER/MALE/01NOBORDER")
      (footprint "eagle-import:HEADER_MALE_01_NOBORDER")
      (fields (field (name "SPICEPREFIX") "X"))
      (libsource (lib "eagle-import") (part "HEADER/MALE/01NOBORDER"))
    )
    (comp (ref "P5")
      (value "HEADER/MALE/01NOBORDER")
      (footprint "eagle-import:HEADER_MALE_01_NOBORDER")
      (fields (field (name "SPICEPREFIX") "X"))
      (libsource (lib "eagle-import") (part "HEADER/MALE/01NOBORDER"))
    )
    (comp (ref "P6")
      (value "HEADER/MALE/01NOBORDER")
      (footprint "eagle-import:HEADER_MALE_01_NOBORDER")
      (fields (field (name "SPICEPREFIX") "X"))
      (libsource (lib "eagle-import") (part "HEADER/MALE/01NOBORDER"))
    )
    (comp (ref "P7")
      (value "HEADER/MALE/01NOBORDER")
      (footprint "eagle-import:HEADER_MALE_01_NOBORDER")
      (fields (field (name "SPICEPREFIX") "X"))
      (libsource (lib "eagle-import") (part "HEADER/MALE/01NOBORDER"))
    )
    (comp (ref "P8")
      (value "HEADER/MALE/01NOBORDER")
      (footprint "eagle-import:HEADER_MALE_01_NOBORDER")
      (fields (field (name "SPICEPREFIX") "X"))
      (libsource (lib "eagle-import") (part "HEADER/MALE/01NOBORDER"))
    )
    (comp (ref "P9")
      (value "HEADER/MALE/01NOBORDER")
      (footprint "eagle-import:HEADER_MALE_01_NOBORDER")
      (fields (field (name "SPICEPREFIX") "X"))
      (libsource (lib "eagle-import") (part "HEADER/MALE/01NOBORDER"))
    )
    (comp (ref "P10")
      (value "HEADER/MALE/01NOBORDER")
      (footprint "eagle-import:HEADER_MALE_01_NOBORDER")
      (fields (field (name "SPICEPREFIX") "X"))
      (libsource (lib "eagle-import") (part "HEADER/MALE/01NOBORDER"))
    )
    (comp (ref "P11")
      (value "HEADER/MALE/01NOBORDER")
      (footprint "eagle-import:HEADER_MALE_01_NOBORDER")
      (fields (field (name "SPICEPREFIX") "X"))
      (libsource (lib "eagle-import") (part "HEADER/MALE/01NOBORDER"))
    )
    (comp (ref "P12")
      (value "HEADER/MALE/01NOBORDER")
      (footprint "eagle-import:HEADER_MALE_01_NOBORDER")
      (fields (field (name "SPICEPREFIX") "X"))
      (libsource (lib "eagle-import") (part "HEADER/MALE/01NOBORDER"))
    )
    (comp (ref "P13")
      (value "HEADER/MALE/01NOBORDER")
      (footprint "eagle-import:HEADER_MALE_01_NOBORDER")
      (fields (field (name "SPICEPREFIX") "X"))
      (libsource (lib "eagle-import") (part "HEADER/MALE/01NOBORDER"))
    )
    (comp (ref "P14")
      (value "HEADER/MALE/01NOBORDER")
      (footprint "eagle-import:HEADER_MALE_01_NOBORDER")
      (fields (field (name "SPICEPREFIX") "X"))
      (libsource (lib "eagle-import") (part "HEADER/MALE/01NOBORDER"))
    )
    (comp (ref "P15")
      (value "HEADER/MALE/01NOBORDER")
      (footprint "eagle-import:HEADER_MALE_01_NOBORDER")
      (fields (field (name "SPICEPREFIX") "X"))
      (libsource (lib "eagle-import") (part "HEADER/MALE/01NOBORDER"))
    )
    (comp (ref "P16")
      (value "HEADER/MALE/01NOBORDER")
      (footprint "eagle-import:HEADER_MALE_01_NOBORDER")
      (fields (field (name "SPICEPREFIX") "X"))
      (libsource (lib "eagle-import") (part "HEADER/MALE/01NOBORDER"))
    )
    (comp (ref "P17")
      (value "HEADER/MALE/01NOBORDER")
      (footprint "eagle-import:HEADER_MALE_01_NOBORDER")
      (fields (field (name "SPICEPREFIX") "X"))
      (libsource (lib "eagle-import") (part "HEADER/MALE/01NOBORDER"))
    )
    (comp (ref "P18")
      (value "HEADER/MALE/01NOBORDER")
      (footprint "eagle-import:HEADER_MALE_01_NOBORDER")
      (fields (field (name "SPICEPREFIX") "X"))
      (libsource (lib "eagle-import") (part "HEADER/MALE/01NOBORDER"))
    )
    (comp (ref "P19")
      (value "HEADER/MALE/01NOBORDER")
      (footprint "eagle-import:HEADER_MALE_01_NOBORDER")
      (fields (field (name "SPICEPREFIX") "X"))
      (libsource (lib "eagle-import") (part "HEADER/MALE/01NOBORDER"))
    )
    (comp (ref "P21")
      (value "HEADER/MALE/01NOBORDER")
      (footprint "eagle-import:HEADER_MALE_01_NOBORDER")
      (fields (field (name "SPICEPREFIX") "X"))
      (libsource (lib "eagle-import") (part "HEADER/MALE/01NOBORDER"))
    )
    (comp (ref "P22")
      (value "HEADER/MALE/01NOBORDER")
      (footprint "eagle-import:HEADER_MALE_01_NOBORDER")
      (fields (field (name "SPICEPREFIX") "X"))
      (libsource (lib "eagle-import") (part "HEADER/MALE/01NOBORDER"))
    )
    (comp (ref "P23")
      (value "HEADER/MALE/01NOBORDER")
      (footprint "eagle-import:HEADER_MALE_01_NOBORDER")
      (fields (field (name "SPICEPREFIX") "X"))
      (libsource (lib "eagle-import") (part "HEADER/MALE/01NOBORDER"))
    )
    (comp (ref "P24")
      (value "HEADER/MALE/01NOBORDER")
      (footprint "eagle-import:HEADER_MALE_01_NOBORDER")
      (fields (field (name "SPICEPREFIX") "X"))
      (libsource (lib "eagle-import") (part "HEADER/MALE/01NOBORDER"))
    )
    (comp (ref "P25")
      (value "HEADER/MALE/01NOBORDER")
      (footprint "eagle-import:HEADER_MALE_01_NOBORDER")
      (fields (field (name "SPICEPREFIX") "X"))
      (libsource (lib "eagle-import") (part "HEADER/MALE/01NOBORDER"))
    )
    (comp (ref "P26")
      (value "HEADER/MALE/01NOBORDER")
      (footprint "eagle-import:HEADER_MALE_01_NOBORDER")
      (fields (field (name "SPICEPREFIX") "X"))
      (libsource (lib "eagle-import") (part "HEADER/MALE/01NOBORDER"))
    )
    (comp (ref "P27")
      (value "HEADER/MALE/01NOBORDER")
      (footprint "eagle-import:HEADER_MALE_01_NOBORDER")
      (fields (field (name "SPICEPREFIX") "X"))
      (libsource (lib "eagle-import") (part "HEADER/MALE/01NOBORDER"))
    )
    (comp (ref "P28")
      (value "HEADER/MALE/01NOBORDER")
      (footprint "eagle-import:HEADER_MALE_01_NOBORDER")
      (fields (field (name "SPICEPREFIX") "X"))
      (libsource (lib "eagle-import") (part "HEADER/MALE/01NOBORDER"))
    )
    (comp (ref "P29")
      (value "HEADER/MALE/01NOBORDER")
      (footprint "eagle-import:HEADER_MALE_01_NOBORDER")
      (fields (field (name "SPICEPREFIX") "X"))
      (libsource (lib "eagle-import") (part "HEADER/MALE/01NOBORDER"))
    )
    (comp (ref "P30")
      (value "HEADER/MALE/01NOBORDER")
      (footprint "eagle-import:HEADER_MALE_01_NOBORDER")
      (fields (field (name "SPICEPREFIX") "X"))
      (libsource (lib "eagle-import") (part "HEADER/MALE/01NOBORDER"))
    )
    (comp (ref "P31")
      (value "HEADER/MALE/01NOBORDER")
      (footprint "eagle-import:HEADER_MALE_01_NOBORDER")
      (fields (field (name "SPICEPREFIX") "X"))
      (libsource (lib "eagle-import") (part "HEADER/MALE/01NOBORDER"))
    )
    (comp (ref "P32")
      (value "HEADER/MALE/01NOBORDER")
      (footprint "eagle-import:HEADER_MALE_01_NOBORDER")
      (fields (field (name "SPICEPREFIX") "X"))
      (libsource (lib "eagle-import") (part "HEADER/MALE/01NOBORDER"))
    )
    (comp (ref "P33")
      (value "HEADER/MALE/01NOBORDER")
      (footprint "eagle-import:HEADER_MALE_01_NOBORDER")
      (fields (field (name "SPICEPREFIX") "X"))
      (libsource (lib "eagle-import") (part "HEADER/MALE/01NOBORDER"))
    )
    (comp (ref "P34")
      (value "HEADER/MALE/01NOBORDER")
      (footprint "eagle-import:HEADER_MALE_01_NOBORDER")
      (fields (field (name "SPICEPREFIX") "X"))
      (libsource (lib "eagle-import") (part "HEADER/MALE/01NOBORDER"))
    )
    (comp (ref "P35")
      (value "HEADER/MALE/01NOBORDER")
      (footprint "eagle-import:HEADER_MALE_01_NOBORDER")
      (fields (field (name "SPICEPREFIX") "X"))
      (libsource (lib "eagle-import") (part "HEADER/MALE/01NOBORDER"))
    )
    (comp (ref "P36")
      (value "HEADER/MALE/01NOBORDER")
      (footprint "eagle-import:HEADER_MALE_01_NOBORDER")
      (fields (field (name "SPICEPREFIX") "X"))
      (libsource (lib "eagle-import") (part "HEADER/MALE/01NOBORDER"))
    )
    (comp (ref "P37")
      (value "HEADER/MALE/01NOBORDER")
      (footprint "eagle-import:HEADER_MALE_01_NOBORDER")
      (fields (field (name "SPICEPREFIX") "X"))
      (libsource (lib "eagle-import") (part "HEADER/MALE/01NOBORDER"))
    )
    (comp (ref "P38")
      (value "HEADER/MALE/01NOBORDER")
      (footprint "eagle-import:HEADER_MALE_01_NOBORDER")
      (fields (field (name "SPICEPREFIX") "X"))
      (libsource (lib "eagle-import") (part "HEADER/MALE/01NOBORDER"))
    )
    (comp (ref "P39")
      (value "HEADER/MALE/01NOBORDER")
      (footprint "eagle-import:HEADER_MALE_01_NOBORDER")
      (fields (field (name "SPICEPREFIX") "X"))
      (libsource (lib "eagle-import") (part "HEADER/MALE/01NOBORDER"))
    )
    (comp (ref "P40")
      (value "HEADER/MALE/01NOBORDER")
      (footprint "eagle-import:HEADER_MALE_01_NOBORDER")
      (fields (field (name "SPICEPREFIX") "X"))
      (libsource (lib "eagle-import") (part "HEADER/MALE/01NOBORDER"))
    )
    (comp (ref "P41")
      (value "HEADER/MALE/01NOBORDER")
      (footprint "eagle-import:HEADER_MALE_01_NOBORDER")
      (fields (field (name "SPICEPREFIX") "X"))
      (libsource (lib "eagle-import") (part "HEADER/MALE/01NOBORDER"))
    )
    (comp (ref "P42")
      (value "HEADER/MALE/01NOBORDER")
      (footprint "eagle-import:HEADER_MALE_01_NOBORDER")
      (fields (field (name "SPICEPREFIX") "X"))
      (libsource (lib "eagle-import") (part "HEADER/MALE/01NOBORDER"))
    )
    (comp (ref "P44")
      (value "HEADER/MALE/01NOBORDER")
      (footprint "eagle-import:HEADER_MALE_01_NOBORDER")
      (fields (field (name "SPICEPREFIX") "X"))
      (libsource (lib "eagle-import") (part "HEADER/MALE/01NOBORDER"))
    )
    (comp (ref "P45")
      (value "HEADER/MALE/01NOBORDER")
      (footprint "eagle-import:HEADER_MALE_01_NOBORDER")
      (fields (field (name "SPICEPREFIX") "X"))
      (libsource (lib "eagle-import") (part "HEADER/MALE/01NOBORDER"))
    )
    (comp (ref "P46")
      (value "HEADER/MALE/01NOBORDER")
      (footprint "eagle-import:HEADER_MALE_01_NOBORDER")
      (fields (field (name "SPICEPREFIX") "X"))
      (libsource (lib "eagle-import") (part "HEADER/MALE/01NOBORDER"))
    )
    (comp (ref "P47")
      (value "HEADER/MALE/01NOBORDER")
      (footprint "eagle-import:HEADER_MALE_01_NOBORDER")
      (fields (field (name "SPICEPREFIX") "X"))
      (libsource (lib "eagle-import") (part "HEADER/MALE/01NOBORDER"))
    )
    (comp (ref "P49")
      (value "HEADER/MALE/01NOBORDER")
      (footprint "eagle-import:HEADER_MALE_01_NOBORDER")
      (fields (field (name "SPICEPREFIX") "X"))
      (libsource (lib "eagle-import") (part "HEADER/MALE/01NOBORDER"))
    )
    (comp (ref "P50")
      (value "HEADER/MALE/01NOBORDER")
      (footprint "eagle-import:HEADER_MALE_01_NOBORDER")
      (fields (field (name "SPICEPREFIX") "X"))
      (libsource (lib "eagle-import") (part "HEADER/MALE/01NOBORDER"))
    )
    (comp (ref "PT1")
      (value "HEADER/MALE/01")
      (footprint "eagle-import:HEADER_MALE_01")
      (fields (field (name "SPICEPREFIX") "X"))
      (libsource (lib "eagle-import") (part "HEADER/MALE/01"))
    )
    (comp (ref "PT2")
      (value "HEADER/MALE/01")
      (footprint "eagle-import:HEADER_MALE_01")
      (fields (field (name "SPICEPREFIX") "X"))
      (libsource (lib "eagle-import") (part "HEADER/MALE/01"))
    )
    (comp (ref "PT3")
      (value "HEADER/MALE/01")
      (footprint "eagle-import:HEADER_MALE_01")
      (fields (field (name "SPICEPREFIX") "X"))
      (libsource (lib "eagle-import") (part "HEADER/MALE/01"))
    )
    (comp (ref "PT4")
      (value "HEADER/MALE/01")
      (footprint "eagle-import:HEADER_MALE_01")
      (fields (field (name "SPICEPREFIX") "X"))
      (libsource (lib "eagle-import") (part "HEADER/MALE/01"))
    )
    (comp (ref "PT5")
      (value "HEADER/MALE/01")
      (footprint "eagle-import:HEADER_MALE_01")
      (fields (field (name "SPICEPREFIX") "X"))
      (libsource (lib "eagle-import") (part "HEADER/MALE/01"))
    )
    (comp (ref "PT6")
      (value "HEADER/MALE/01")
      (footprint "eagle-import:HEADER_MALE_01")
      (fields (field (name "SPICEPREFIX") "X"))
      (libsource (lib "eagle-import") (part "HEADER/MALE/01"))
    )
    (comp (ref "PT7")
      (value "HEADER/MALE/01")
      (footprint "eagle-import:HEADER_MALE_01")
      (fields (field (name "SPICEPREFIX") "X"))
      (libsource (lib "eagle-import") (part "HEADER/MALE/01"))
    )
    (comp (ref "PT8")
      (value "HEADER/MALE/01")
      (footprint "eagle-import:HEADER_MALE_01")
      (fields (field (name "SPICEPREFIX") "X"))
      (libsource (lib "eagle-import") (part "HEADER/MALE/01"))
    )
    (comp (ref "Q1")
      (value "BF170")
      (footprint "eagle-import:SOT23")
      (libsource (lib "eagle-import") (part "BS170SOT23"))
    )
    (comp (ref "Q2")
      (value "BF170")
      (footprint "eagle-import:SOT23")
      (libsource (lib "eagle-import") (part "BS170SOT23"))
    )
    (comp (ref "Q3")
      (value "BF170")
      (footprint "eagle-import:SOT23")
      (libsource (lib "eagle-import") (part "BS170SOT23"))
    )
    (comp (ref "Q4")
      (value "BF170")
      (footprint "eagle-import:SOT23")
      (libsource (lib "eagle-import") (part "BS170SOT23"))
    )
    (comp (ref "Q5")
      (value "BF170")
      (footprint "eagle-import:SOT23")
      (libsource (lib "eagle-import") (part "BS170SOT23"))
    )
    (comp (ref "Q6")
      (value "BF170")
      (footprint "eagle-import:SOT23")
      (libsource (lib "eagle-import") (part "BS170SOT23"))
    )
    (comp (ref "Q7")
      (value "BF170")
      (footprint "eagle-import:SOT23")
      (libsource (lib "eagle-import") (part "BS170SOT23"))
    )
    (comp (ref "Q8")
      (value "BF170")
      (footprint "eagle-import:SOT23")
      (libsource (lib "eagle-import") (part "BS170SOT23"))
    )
    (comp (ref "Q9")
      (value "BF170")
      (footprint "eagle-import:SOT23")
      (libsource (lib "eagle-import") (part "BS170SOT23"))
    )
    (comp (ref "Q10")
      (value "BF170")
      (footprint "eagle-import:SOT23")
      (libsource (lib "eagle-import") (part "BS170SOT23"))
    )
    (comp (ref "Q11")
      (value "BF170")
      (footprint "eagle-import:SOT23")
      (libsource (lib "eagle-import") (part "BS170SOT23"))
    )
    (comp (ref "Q12")
      (value "BF170")
      (footprint "eagle-import:SOT23")
      (libsource (lib "eagle-import") (part "BS170SOT23"))
    )
    (comp (ref "Q13")
      (value "BF170")
      (footprint "eagle-import:SOT23")
      (libsource (lib "eagle-import") (part "BS170SOT23"))
    )
    (comp (ref "Q14")
      (value "BF170")
      (footprint "eagle-import:SOT23")
      (libsource (lib "eagle-import") (part "BS170SOT23"))
    )
    (comp (ref "Q15")
      (value "BF170")
      (footprint "eagle-import:SOT23")
      (libsource (lib "eagle-import") (part "BS170SOT23"))
    )
    (comp (ref "Q16")
      (value "BF170")
      (footprint "eagle-import:SOT23")
      (libsource (lib "eagle-import") (part "BS170SOT23"))
    )
    (comp (ref "R1")
      (value "120k")
      (footprint "eagle-import:R0603")
      (libsource (lib "eagle-import") (part "RESISTOR"))
    )
    (comp (ref "R2")
      (value "30k")
      (footprint "eagle-import:R0603")
      (libsource (lib "eagle-import") (part "RESISTOR"))
    )
    (comp (ref "R3")
      (value "1k")
      (footprint "eagle-import:R0603")
      (libsource (lib "eagle-import") (part "RESISTOR"))
    )
    (comp (ref "R4")
      (value "120k")
      (footprint "eagle-import:R0603")
      (libsource (lib "eagle-import") (part "RESISTOR"))
    )
    (comp (ref "R5")
      (value "30k")
      (footprint "eagle-import:R0603")
      (libsource (lib "eagle-import") (part "RESISTOR"))
    )
    (comp (ref "R6")
      (value "1k")
      (footprint "eagle-import:R0603")
      (libsource (lib "eagle-import") (part "RESISTOR"))
    )
    (comp (ref "R7")
      (value "2K")
      (footprint "eagle-import:R0603")
      (libsource (lib "eagle-import") (part "RESISTOR"))
    )
    (comp (ref "R8")
      (value "33k")
      (footprint "eagle-import:R0603")
      (libsource (lib "eagle-import") (part "RESISTOR"))
    )
    (comp (ref "R9")
      (value "120k")
      (footprint "eagle-import:R0603")
      (libsource (lib "eagle-import") (part "RESISTOR"))
    )
    (comp (ref "R10")
      (value "30k")
      (footprint "eagle-import:R0603")
      (libsource (lib "eagle-import") (part "RESISTOR"))
    )
    (comp (ref "R11")
      (value "100k")
      (footprint "eagle-import:R0603")
      (libsource (lib "eagle-import") (part "RESISTOR"))
    )
    (comp (ref "R12")
      (value "100k")
      (footprint "eagle-import:R0603")
      (libsource (lib "eagle-import") (part "RESISTOR"))
    )
    (comp (ref "R13")
      (value "100k")
      (footprint "eagle-import:R0603")
      (libsource (lib "eagle-import") (part "RESISTOR"))
    )
    (comp (ref "R14")
      (value "1k")
      (footprint "eagle-import:R0603")
      (libsource (lib "eagle-import") (part "RESISTOR"))
    )
    (comp (ref "R15")
      (value "33k")
      (footprint "eagle-import:R0603")
      (libsource (lib "eagle-import") (part "RESISTOR"))
    )
    (comp (ref "R16")
      (value "120k")
      (footprint "eagle-import:R0603")
      (libsource (lib "eagle-import") (part "RESISTOR"))
    )
    (comp (ref "R17")
      (value "30k")
      (footprint "eagle-import:R0603")
      (libsource (lib "eagle-import") (part "RESISTOR"))
    )
    (comp (ref "R18")
      (value "1k")
      (footprint "eagle-import:R0603")
      (libsource (lib "eagle-import") (part "RESISTOR"))
    )
    (comp (ref "R19")
      (value "120k")
      (footprint "eagle-import:R0603")
      (libsource (lib "eagle-import") (part "RESISTOR"))
    )
    (comp (ref "R20")
      (value "30k")
      (footprint "eagle-import:R0603")
      (libsource (lib "eagle-import") (part "RESISTOR"))
    )
    (comp (ref "R21")
      (value "33k")
      (footprint "eagle-import:R0603")
      (libsource (lib "eagle-import") (part "RESISTOR"))
    )
    (comp (ref "R22")
      (value "100k")
      (footprint "eagle-import:R0603")
      (libsource (lib "eagle-import") (part "RESISTOR"))
    )
    (comp (ref "R23")
      (value "100k")
      (footprint "eagle-import:R0603")
      (libsource (lib "eagle-import") (part "RESISTOR"))
    )
    (comp (ref "R24")
      (value "100k")
      (footprint "eagle-import:R0603")
      (libsource (lib "eagle-import") (part "RESISTOR"))
    )
    (comp (ref "R25")
      (value "33k")
      (footprint "eagle-import:R0603")
      (libsource (lib "eagle-import") (part "RESISTOR"))
    )
    (comp (ref "R26")
      (value "100k")
      (footprint "eagle-import:R0603")
      (libsource (lib "eagle-import") (part "RESISTOR"))
    )
    (comp (ref "R27")
      (value "100k")
      (footprint "eagle-import:R0603")
      (libsource (lib "eagle-import") (part "RESISTOR"))
    )
    (comp (ref "R28")
      (value "100k")
      (footprint "eagle-import:R0603")
      (libsource (lib "eagle-import") (part "RESISTOR"))
    )
    (comp (ref "R29")
      (value "100k")
      (footprint "eagle-import:R0603")
      (libsource (lib "eagle-import") (part "RESISTOR"))
    )
    (comp (ref "R30")
      (value "33k")
      (footprint "eagle-import:R0603")
      (libsource (lib "eagle-import") (part "RESISTOR"))
    )
    (comp (ref "R31")
      (value "100k")
      (footprint "eagle-import:R0603")
      (libsource (lib "eagle-import") (part "RESISTOR"))
    )
    (comp (ref "R32")
      (value "100k")
      (footprint "eagle-import:R0603")
      (libsource (lib "eagle-import") (part "RESISTOR"))
    )
    (comp (ref "R33")
      (value "100k")
      (footprint "eagle-import:R0603")
      (libsource (lib "eagle-import") (part "RESISTOR"))
    )
    (comp (ref "R34")
      (value "33k")
      (footprint "eagle-import:R0603")
      (libsource (lib "eagle-import") (part "RESISTOR"))
    )
    (comp (ref "R35")
      (value "100k")
      (footprint "eagle-import:R0603")
      (libsource (lib "eagle-import") (part "RESISTOR"))
    )
    (comp (ref "R36")
      (value "100k")
      (footprint "eagle-import:R0603")
      (libsource (lib "eagle-import") (part "RESISTOR"))
    )
    (comp (ref "R37")
      (value "100k")
      (footprint "eagle-import:R0603")
      (libsource (lib "eagle-import") (part "RESISTOR"))
    )
    (comp (ref "R38")
      (value "1k")
      (footprint "eagle-import:R0603")
      (libsource (lib "eagle-import") (part "RESISTOR"))
    )
    (comp (ref "R39")
      (value "120k")
      (footprint "eagle-import:R0603")
      (libsource (lib "eagle-import") (part "RESISTOR"))
    )
    (comp (ref "R40")
      (value "30k")
      (footprint "eagle-import:R0603")
      (libsource (lib "eagle-import") (part "RESISTOR"))
    )
    (comp (ref "R41")
      (value "1k")
      (footprint "eagle-import:R0603")
      (libsource (lib "eagle-import") (part "RESISTOR"))
    )
    (comp (ref "R42")
      (value "120k")
      (footprint "eagle-import:R0603")
      (libsource (lib "eagle-import") (part "RESISTOR"))
    )
    (comp (ref "R43")
      (value "30k")
      (footprint "eagle-import:R0603")
      (libsource (lib "eagle-import") (part "RESISTOR"))
    )
    (comp (ref "R44")
      (value "1k")
      (footprint "eagle-import:R0603")
      (libsource (lib "eagle-import") (part "RESISTOR"))
    )
    (comp (ref "R45")
      (value "120k")
      (footprint "eagle-import:R0603")
      (libsource (lib "eagle-import") (part "RESISTOR"))
    )
    (comp (ref "R46")
      (value "30k")
      (footprint "eagle-import:R0603")
      (libsource (lib "eagle-import") (part "RESISTOR"))
    )
    (comp (ref "R47")
      (value "1k")
      (footprint "eagle-import:R0603")
      (libsource (lib "eagle-import") (part "RESISTOR"))
    )
    (comp (ref "R48")
      (value "120k")
      (footprint "eagle-import:R0603")
      (libsource (lib "eagle-import") (part "RESISTOR"))
    )
    (comp (ref "R49")
      (value "120k")
      (footprint "eagle-import:R0603")
      (libsource (lib "eagle-import") (part "RESISTOR"))
    )
    (comp (ref "R50")
      (value "120k")
      (footprint "eagle-import:R0603")
      (libsource (lib "eagle-import") (part "RESISTOR"))
    )
    (comp (ref "R51")
      (value "120k")
      (footprint "eagle-import:R0603")
      (libsource (lib "eagle-import") (part "RESISTOR"))
    )
    (comp (ref "R52")
      (value "120k")
      (footprint "eagle-import:R0603")
      (libsource (lib "eagle-import") (part "RESISTOR"))
    )
    (comp (ref "R53")
      (value "120k")
      (footprint "eagle-import:R0603")
      (libsource (lib "eagle-import") (part "RESISTOR"))
    )
    (comp (ref "R54")
      (value "120k")
      (footprint "eagle-import:R0603")
      (libsource (lib "eagle-import") (part "RESISTOR"))
    )
    (comp (ref "R55")
      (value "120k")
      (footprint "eagle-import:R0603")
      (libsource (lib "eagle-import") (part "RESISTOR"))
    )
    (comp (ref "R56")
      (value "10k")
      (footprint "eagle-import:R0603")
      (libsource (lib "eagle-import") (part "RESISTOR"))
    )
    (comp (ref "R57")
      (value "10k")
      (footprint "eagle-import:R0603")
      (libsource (lib "eagle-import") (part "RESISTOR"))
    )
    (comp (ref "R58")
      (value "10k")
      (footprint "eagle-import:R0603")
      (libsource (lib "eagle-import") (part "RESISTOR"))
    )
    (comp (ref "R59")
      (value "10k")
      (footprint "eagle-import:R0603")
      (libsource (lib "eagle-import") (part "RESISTOR"))
    )
    (comp (ref "R60")
      (value "10k")
      (footprint "eagle-import:R0603")
      (libsource (lib "eagle-import") (part "RESISTOR"))
    )
    (comp (ref "R61")
      (value "10k")
      (footprint "eagle-import:R0603")
      (libsource (lib "eagle-import") (part "RESISTOR"))
    )
    (comp (ref "R62")
      (value "100k")
      (footprint "eagle-import:R0603")
      (libsource (lib "eagle-import") (part "RESISTOR"))
    )
    (comp (ref "R63")
      (value "100k")
      (footprint "eagle-import:R0603")
      (libsource (lib "eagle-import") (part "RESISTOR"))
    )
    (comp (ref "R64")
      (value "33k")
      (footprint "eagle-import:R0603")
      (libsource (lib "eagle-import") (part "RESISTOR"))
    )
    (comp (ref "R65")
      (value "100k")
      (footprint "eagle-import:R0603")
      (libsource (lib "eagle-import") (part "RESISTOR"))
    )
    (comp (ref "R66")
      (value "100k")
      (footprint "eagle-import:R0603")
      (libsource (lib "eagle-import") (part "RESISTOR"))
    )
    (comp (ref "R67")
      (value "100k")
      (footprint "eagle-import:R0603")
      (libsource (lib "eagle-import") (part "RESISTOR"))
    )
    (comp (ref "R68")
      (value "33k")
      (footprint "eagle-import:R0603")
      (libsource (lib "eagle-import") (part "RESISTOR"))
    )
    (comp (ref "R69")
      (value "100k")
      (footprint "eagle-import:R0603")
      (libsource (lib "eagle-import") (part "RESISTOR"))
    )
    (comp (ref "R70")
      (value "100k")
      (footprint "eagle-import:R0603")
      (libsource (lib "eagle-import") (part "RESISTOR"))
    )
    (comp (ref "R71")
      (value "100k")
      (footprint "eagle-import:R0603")
      (libsource (lib "eagle-import") (part "RESISTOR"))
    )
    (comp (ref "R72")
      (value "10k")
      (footprint "eagle-import:R0603")
      (libsource (lib "eagle-import") (part "RESISTOR"))
    )
    (comp (ref "R73")
      (value "10k")
      (footprint "eagle-import:R0603")
      (libsource (lib "eagle-import") (part "RESISTOR"))
    )
    (comp (ref "R74")
      (value "10k")
      (footprint "eagle-import:R0603")
      (libsource (lib "eagle-import") (part "RESISTOR"))
    )
    (comp (ref "R75")
      (value "10k")
      (footprint "eagle-import:R0603")
      (libsource (lib "eagle-import") (part "RESISTOR"))
    )
    (comp (ref "R76")
      (value "10k")
      (footprint "eagle-import:R0603")
      (libsource (lib "eagle-import") (part "RESISTOR"))
    )
    (comp (ref "R77")
      (value "10k")
      (footprint "eagle-import:R0603")
      (libsource (lib "eagle-import") (part "RESISTOR"))
    )
    (comp (ref "R78")
      (value "10k")
      (footprint "eagle-import:R0603")
      (libsource (lib "eagle-import") (part "RESISTOR"))
    )
    (comp (ref "R79")
      (value "10k")
      (footprint "eagle-import:R0603")
      (libsource (lib "eagle-import") (part "RESISTOR"))
    )
    (comp (ref "R80")
      (value "10k")
      (footprint "eagle-import:R0603")
      (libsource (lib "eagle-import") (part "RESISTOR"))
    )
    (comp (ref "R81")
      (value "10k")
      (footprint "eagle-import:R0603")
      (libsource (lib "eagle-import") (part "RESISTOR"))
    )
    (comp (ref "R82")
      (value "1k")
      (footprint "eagle-import:R0603")
      (libsource (lib "eagle-import") (part "RESISTOR"))
    )
    (comp (ref "R83")
      (value "120k")
      (footprint "eagle-import:R0603")
      (libsource (lib "eagle-import") (part "RESISTOR"))
    )
    (comp (ref "R84")
      (value "120k")
      (footprint "eagle-import:R0603")
      (libsource (lib "eagle-import") (part "RESISTOR"))
    )
    (comp (ref "R85")
      (value "120k")
      (footprint "eagle-import:R0603")
      (libsource (lib "eagle-import") (part "RESISTOR"))
    )
    (comp (ref "R86")
      (value "120k")
      (footprint "eagle-import:R0603")
      (libsource (lib "eagle-import") (part "RESISTOR"))
    )
    (comp (ref "R87")
      (value "120k")
      (footprint "eagle-import:R0603")
      (libsource (lib "eagle-import") (part "RESISTOR"))
    )
    (comp (ref "R88")
      (value "120k")
      (footprint "eagle-import:R0603")
      (libsource (lib "eagle-import") (part "RESISTOR"))
    )
    (comp (ref "R89")
      (value "120k")
      (footprint "eagle-import:R0603")
      (libsource (lib "eagle-import") (part "RESISTOR"))
    )
    (comp (ref "R90")
      (value "120k")
      (footprint "eagle-import:R0603")
      (libsource (lib "eagle-import") (part "RESISTOR"))
    )
    (comp (ref "R91")
      (value "0R")
      (footprint "eagle-import:R0603")
      (libsource (lib "eagle-import") (part "RESISTOR"))
    )
    (comp (ref "R92")
      (value "0R")
      (footprint "eagle-import:R0603")
      (libsource (lib "eagle-import") (part "RESISTOR"))
    )
    (comp (ref "R93")
      (value "0R")
      (footprint "eagle-import:R0603")
      (libsource (lib "eagle-import") (part "RESISTOR"))
    )
    (comp (ref "R94")
      (value "0R")
      (footprint "eagle-import:R0603")
      (libsource (lib "eagle-import") (part "RESISTOR"))
    )
    (comp (ref "R99")
      (value "10k")
      (footprint "eagle-import:R0603")
      (libsource (lib "eagle-import") (part "RESISTOR"))
    )
    (comp (ref "R100")
      (value "10k")
      (footprint "eagle-import:R0603")
      (libsource (lib "eagle-import") (part "RESISTOR"))
    )
    (comp (ref "R101")
      (value "10k")
      (footprint "eagle-import:R0603")
      (libsource (lib "eagle-import") (part "RESISTOR"))
    )
    (comp (ref "R102")
      (value "10k")
      (footprint "eagle-import:R0603")
      (libsource (lib "eagle-import") (part "RESISTOR"))
    )
    (comp (ref "R103")
      (value "10k")
      (footprint "eagle-import:R0603")
      (libsource (lib "eagle-import") (part "RESISTOR"))
    )
    (comp (ref "R104")
      (value "10k")
      (footprint "eagle-import:R0603")
      (libsource (lib "eagle-import") (part "RESISTOR"))
    )
    (comp (ref "R105")
      (value "10k")
      (footprint "eagle-import:R0603")
      (libsource (lib "eagle-import") (part "RESISTOR"))
    )
    (comp (ref "R106")
      (value "10k")
      (footprint "eagle-import:R0603")
      (libsource (lib "eagle-import") (part "RESISTOR"))
    )
    (comp (ref "R107")
      (value "10k")
      (footprint "eagle-import:R0603")
      (libsource (lib "eagle-import") (part "RESISTOR"))
    )
    (comp (ref "R108")
      (value "10k")
      (footprint "eagle-import:R0603")
      (libsource (lib "eagle-import") (part "RESISTOR"))
    )
    (comp (ref "R109")
      (value "10k")
      (footprint "eagle-import:R0603")
      (libsource (lib "eagle-import") (part "RESISTOR"))
    )
    (comp (ref "R110")
      (value "10k")
      (footprint "eagle-import:R0603")
      (libsource (lib "eagle-import") (part "RESISTOR"))
    )
    (comp (ref "R111")
      (value "10k")
      (footprint "eagle-import:R0603")
      (libsource (lib "eagle-import") (part "RESISTOR"))
    )
    (comp (ref "R112")
      (value "10k")
      (footprint "eagle-import:R0603")
      (libsource (lib "eagle-import") (part "RESISTOR"))
    )
    (comp (ref "R113")
      (value "10k")
      (footprint "eagle-import:R0603")
      (libsource (lib "eagle-import") (part "RESISTOR"))
    )
    (comp (ref "R114")
      (value "10k")
      (footprint "eagle-import:R0603")
      (libsource (lib "eagle-import") (part "RESISTOR"))
    )
    (comp (ref "R115")
      (value "2K")
      (footprint "eagle-import:R0603")
      (libsource (lib "eagle-import") (part "RESISTOR"))
    )
    (comp (ref "R116")
      (value "2K")
      (footprint "eagle-import:R0603")
      (libsource (lib "eagle-import") (part "RESISTOR"))
    )
  )
  (nets
    (net (code "1") (name "+12V") (class "Default")
      (node (ref "+V") (pin "1") (pinfunction "3_1") (pintype "passive"))
      (node (ref "+V1") (pin "1") (pinfunction "3_1") (pintype "passive"))
      (node (ref "+V2") (pin "1") (pinfunction "3_1") (pintype "passive"))
      (node (ref "+V3") (pin "1") (pinfunction "3_1") (pintype "passive"))
      (node (ref "+V4") (pin "1") (pinfunction "3_1") (pintype "passive"))
      (node (ref "+V5") (pin "1") (pinfunction "3_1") (pintype "passive"))
      (node (ref "C1") (pin "+") (pinfunction "+_+") (pintype "passive"))
      (node (ref "C23") (pin "2") (pinfunction "2_2") (pintype "passive"))
      (node (ref "C26") (pin "2") (pinfunction "2_2") (pintype "passive"))
      (node (ref "IC1") (pin "4") (pinfunction "V+_4") (pintype "power_in"))
      (node (ref "IC5") (pin "4") (pinfunction "V+_4") (pintype "power_in"))
      (node (ref "L1") (pin "1") (pinfunction "1_1") (pintype "passive"))
      (node (ref "L2") (pin "1") (pinfunction "1_1") (pintype "passive"))
    )
    (net (code "2") (name "-12V") (class "Default")
      (node (ref "-V") (pin "1") (pinfunction "3_1") (pintype "passive"))
      (node (ref "-V1") (pin "1") (pinfunction "3_1") (pintype "passive"))
      (node (ref "-V2") (pin "1") (pinfunction "3_1") (pintype "passive"))
      (node (ref "-V3") (pin "1") (pinfunction "3_1") (pintype "passive"))
      (node (ref "-V4") (pin "1") (pinfunction "3_1") (pintype "passive"))
      (node (ref "-V5") (pin "1") (pinfunction "3_1") (pintype "passive"))
      (node (ref "C2") (pin "-") (pinfunction "-_-") (pintype "passive"))
      (node (ref "C24") (pin "1") (pinfunction "1_1") (pintype "passive"))
      (node (ref "C25") (pin "1") (pinfunction "1_1") (pintype "passive"))
      (node (ref "IC1") (pin "11") (pinfunction "V-_11") (pintype "power_in"))
      (node (ref "IC5") (pin "11") (pinfunction "V-_11") (pintype "power_in"))
      (node (ref "R7") (pin "2") (pinfunction "2_2") (pintype "passive"))
    )
    (net (code "3") (name "/-5VREF") (class "Default")
      (node (ref "-5V") (pin "1") (pinfunction "3_1") (pintype "passive"))
      (node (ref "-5V1") (pin "1") (pinfunction "3_1") (pintype "passive"))
      (node (ref "-5V2") (pin "1") (pinfunction "3_1") (pintype "passive"))
      (node (ref "-5V3") (pin "1") (pinfunction "3_1") (pintype "passive"))
      (node (ref "C6") (pin "2") (pinfunction "2_2") (pintype "passive"))
      (node (ref "IC8") (pin "2") (pinfunction "A_2") (pintype "output"))
      (node (ref "R13") (pin "1") (pinfunction "1_1") (pintype "passive"))
      (node (ref "R24") (pin "1") (pinfunction "1_1") (pintype "passive"))
      (node (ref "R26") (pin "1") (pinfunction "1_1") (pintype "passive"))
      (node (ref "R29") (pin "1") (pinfunction "1_1") (pintype "passive"))
      (node (ref "R33") (pin "1") (pinfunction "1_1") (pintype "passive"))
      (node (ref "R37") (pin "1") (pinfunction "1_1") (pintype "passive"))
      (node (ref "R48") (pin "1") (pinfunction "1_1") (pintype "passive"))
      (node (ref "R49") (pin "1") (pinfunction "1_1") (pintype "passive"))
      (node (ref "R50") (pin "1") (pinfunction "1_1") (pintype "passive"))
      (node (ref "R51") (pin "1") (pinfunction "1_1") (pintype "passive"))
      (node (ref "R52") (pin "1") (pinfunction "1_1") (pintype "passive"))
      (node (ref "R53") (pin "1") (pinfunction "1_1") (pintype "passive"))
      (node (ref "R54") (pin "1") (pinfunction "1_1") (pintype "passive"))
      (node (ref "R55") (pin "1") (pinfunction "1_1") (pintype "passive"))
      (node (ref "R67") (pin "1") (pinfunction "1_1") (pintype "passive"))
      (node (ref "R7") (pin "1") (pinfunction "1_1") (pintype "passive"))
      (node (ref "R71") (pin "1") (pinfunction "1_1") (pintype "passive"))
    )
    (net (code "4") (name "/ADC0") (class "Default")
      (node (ref "C7") (pin "2") (pinfunction "2_2") (pintype "passive"))
      (node (ref "IC3") (pin "1") (pinfunction "OUT_1") (pintype "output"))
      (node (ref "IC6") (pin "14-A0/TX3/SPDIF_OUT") (pinfunction "14-A0/TX3/SPDIF_OUT_14-A0/TX3/SPDIF_OUT") (pintype "bidirectional"))
      (node (ref "R8") (pin "2") (pinfunction "2_2") (pintype "passive"))
    )
    (net (code "5") (name "/ADC1") (class "Default")
      (node (ref "C14") (pin "2") (pinfunction "2_2") (pintype "passive"))
      (node (ref "IC3") (pin "14") (pinfunction "OUT_14") (pintype "output"))
      (node (ref "IC6") (pin "15-A1/RX3/SPDIF_IN") (pinfunction "15-A1/RX3/SPDIF_IN_15-A1/RX3/SPDIF_IN") (pintype "bidirectional"))
      (node (ref "R68") (pin "2") (pinfunction "2_2") (pintype "passive"))
    )
    (net (code "6") (name "/ADC2") (class "Default")
      (node (ref "C10") (pin "2") (pinfunction "2_2") (pintype "passive"))
      (node (ref "IC3") (pin "7") (pinfunction "OUT_7") (pintype "output"))
      (node (ref "IC6") (pin "16-A2/RX4/SCL1") (pinfunction "16-A2/RX4/SCL1_16-A2/RX4/SCL1") (pintype "bidirectional"))
      (node (ref "R15") (pin "2") (pinfunction "2_2") (pintype "passive"))
    )
    (net (code "7") (name "/ADC3") (class "Default")
      (node (ref "C11") (pin "2") (pinfunction "2_2") (pintype "passive"))
      (node (ref "IC3") (pin "8") (pinfunction "OUT_8") (pintype "output"))
      (node (ref "IC6") (pin "17-A3/TX4/SDA1") (pinfunction "17-A3/TX4/SDA1_17-A3/TX4/SDA1") (pintype "bidirectional"))
      (node (ref "R64") (pin "2") (pinfunction "2_2") (pintype "passive"))
    )
    (net (code "8") (name "/ADC4") (class "Default")
      (node (ref "C16") (pin "2") (pinfunction "2_2") (pintype "passive"))
      (node (ref "IC4") (pin "1") (pinfunction "OUT_1") (pintype "output"))
      (node (ref "IC6") (pin "20-A6/TX5/LRCLK1") (pinfunction "20-A6/TX5/LRCLK1_20-A6/TX5/LRCLK1") (pintype "bidirectional"))
      (node (ref "R21") (pin "2") (pinfunction "2_2") (pintype "passive"))
    )
    (net (code "9") (name "/ADC5") (class "Default")
      (node (ref "C21") (pin "2") (pinfunction "2_2") (pintype "passive"))
      (node (ref "IC4") (pin "14") (pinfunction "OUT_14") (pintype "output"))
      (node (ref "IC6") (pin "21-A7/RX5/BCLK1") (pinfunction "21-A7/RX5/BCLK1_21-A7/RX5/BCLK1") (pintype "bidirectional"))
      (node (ref "R34") (pin "2") (pinfunction "2_2") (pintype "passive"))
    )
    (net (code "10") (name "/ADC6") (class "Default")
      (node (ref "C17") (pin "2") (pinfunction "2_2") (pintype "passive"))
      (node (ref "IC4") (pin "7") (pinfunction "OUT_7") (pintype "output"))
      (node (ref "IC6") (pin "22-A8/CTX1") (pinfunction "22-A8/CTX1_22-A8/CTX1") (pintype "bidirectional"))
      (node (ref "R25") (pin "2") (pinfunction "2_2") (pintype "passive"))
    )
    (net (code "11") (name "/ADC7") (class "Default")
      (node (ref "C20") (pin "2") (pinfunction "2_2") (pintype "passive"))
      (node (ref "IC4") (pin "8") (pinfunction "OUT_8") (pintype "output"))
      (node (ref "IC6") (pin "23-A9/CRX1/MCLK1") (pinfunction "23-A9/CRX1/MCLK1_23-A9/CRX1/MCLK1") (pintype "bidirectional"))
      (node (ref "R30") (pin "2") (pinfunction "2_2") (pintype "passive"))
    )
    (net (code "12") (name "/ADC8") (class "Default")
      (node (ref "24_4.0-A10") (pin "1") (pinfunction "3_1") (pintype "passive"))
      (node (ref "24_LC-A10") (pin "1") (pinfunction "3_1") (pintype "passive"))
      (node (ref "IC12") (pin "3") (pinfunction "Z_3") (pintype "bidirectional"))
      (node (ref "IC6") (pin "24-A10/TX6/SCL2") (pinfunction "24-A10/TX6/SCL2_24-A10/TX6/SCL2") (pintype "bidirectional"))
      (node (ref "R91") (pin "2") (pinfunction "2_2") (pintype "passive"))
    )
    (net (code "13") (name "/ADC9") (class "Default")
      (node (ref "25_4.0-A11") (pin "1") (pinfunction "3_1") (pintype "passive"))
      (node (ref "25_LC-A11") (pin "1") (pinfunction "3_1") (pintype "passive"))
      (node (ref "IC12") (pin "9") (pinfunction "S2_9") (pintype "input"))
      (node (ref "IC6") (pin "25-A11/RX6/SDA2") (pinfunction "25-A11/RX6/SDA2_25-A11/RX6/SDA2") (pintype "bidirectional"))
      (node (ref "R92") (pin "2") (pinfunction "2_2") (pintype "passive"))
    )
    (net (code "14") (name "/ADC10") (class "Default")
      (node (ref "26_4.0-A12") (pin "1") (pinfunction "3_1") (pintype "passive"))
      (node (ref "26_LC-A12") (pin "1") (pinfunction "3_1") (pintype "passive"))
      (node (ref "IC12") (pin "10") (pinfunction "S1_10") (pintype "input"))
      (node (ref "IC6") (pin "26-A12/MOSI1") (pinfunction "26-A12/MOSI1_26-A12/MOSI1") (pintype "bidirectional"))
      (node (ref "R93") (pin "2") (pinfunction "2_2") (pintype "passive"))
    )
    (net (code "15") (name "/ADC11") (class "Default")
      (node (ref "27_4.0-A13") (pin "1") (pinfunction "3_1") (pintype "passive"))
      (node (ref "IC12") (pin "11") (pinfunction "S0_11") (pintype "input"))
      (node (ref "IC6") (pin "27-A13/SCK1") (pinfunction "27-A13/SCK1_27-A13/SCK1") (pintype "bidirectional"))
      (node (ref "R94") (pin "2") (pinfunction "2_2") (pintype "passive"))
    )
    (net (code "16") (name "/DAC1") (class "Default")
      (node (ref "DAC1") (pin "1") (pinfunction "3_1") (pintype "passive"))
      (node (ref "IC11") (pin "7") (pinfunction "VOUTC_7") (pintype "tri_state"))
      (node (ref "R46") (pin "1") (pinfunction "1_1") (pintype "passive"))
    )
    (net (code "17") (name "/DAC2") (class "Default")
      (node (ref "DAC2") (pin "1") (pinfunction "3_1") (pintype "passive"))
      (node (ref "IC11") (pin "2") (pinfunction "VOUTB_2") (pintype "tri_state"))
      (node (ref "R20") (pin "1") (pinfunction "1_1") (pintype "passive"))
    )
    (net (code "18") (name "/DAC3") (class "Default")
      (node (ref "DAC4") (pin "1") (pinfunction "3_1") (pintype "passive"))
      (node (ref "IC11") (pin "8") (pinfunction "VOUTD_8") (pintype "tri_state"))
      (node (ref "R43") (pin "1") (pinfunction "1_1") (pintype "passive"))
    )
    (net (code "19") (name "/DAC4") (class "Default")
      (node (ref "DAC3") (pin "1") (pinfunction "3_1") (pintype "passive"))
      (node (ref "IC11") (pin "1") (pinfunction "VOUTA_1") (pintype "tri_state"))
      (node (ref "R40") (pin "1") (pinfunction "1_1") (pintype "passive"))
    )
    (net (code "20") (name "/DAC5") (class "Default")
      (node (ref "IC10") (pin "1") (pinfunction "VOUTA_1") (pintype "tri_state"))
      (node (ref "R17") (pin "1") (pinfunction "1_1") (pintype "passive"))
    )
    (net (code "21") (name "/DAC6") (class "Default")
      (node (ref "IC10") (pin "8") (pinfunction "VOUTD_8") (pintype "tri_state"))
      (node (ref "R2") (pin "1") (pinfunction "1_1") (pintype "passive"))
    )
    (net (code "22") (name "/DAC7") (class "Default")
      (node (ref "IC10") (pin "2") (pinfunction "VOUTB_2") (pintype "tri_state"))
      (node (ref "R10") (pin "1") (pinfunction "1_1") (pintype "passive"))
    )
    (net (code "23") (name "/DAC8") (class "Default")
      (node (ref "IC10") (pin "7") (pinfunction "VOUTC_7") (pintype "tri_state"))
      (node (ref "R5") (pin "1") (pinfunction "1_1") (pintype "passive"))
    )
    (net (code "24") (name "/GPA0") (class "Default")
      (node (ref "IC2") (pin "21") (pinfunction "GPA0_21") (pintype "bidirectional"))
      (node (ref "Q1") (pin "2") (pinfunction "S_2") (pintype "passive"))
      (node (ref "R56") (pin "1") (pinfunction "1_1") (pintype "passive"))
    )
    (net (code "25") (name "/GPA1") (class "Default")
      (node (ref "IC2") (pin "22") (pinfunction "GPA1_22") (pintype "bidirectional"))
      (node (ref "Q2") (pin "2") (pinfunction "S_2") (pintype "passive"))
      (node (ref "R57") (pin "1") (pinfunction "1_1") (pintype "passive"))
    )
    (net (code "26") (name "/GPA2") (class "Default")
      (node (ref "IC2") (pin "23") (pinfunction "GPA2_23") (pintype "bidirectional"))
      (node (ref "Q3") (pin "2") (pinfunction "S_2") (pintype "passive"))
      (node (ref "R59") (pin "1") (pinfunction "1_1") (pintype "passive"))
    )
    (net (code "27") (name "/GPA3") (class "Default")
      (node (ref "IC2") (pin "24") (pinfunction "GPA3_24") (pintype "bidirectional"))
      (node (ref "Q4") (pin "2") (pinfunction "S_2") (pintype "passive"))
      (node (ref "R61") (pin "1") (pinfunction "1_1") (pintype "passive"))
    )
    (net (code "28") (name "/GPA4") (class "Default")
      (node (ref "IC2") (pin "25") (pinfunction "GPA4_25") (pintype "bidirectional"))
      (node (ref "Q5") (pin "2") (pinfunction "S_2") (pintype "passive"))
      (node (ref "R73") (pin "1") (pinfunction "1_1") (pintype "passive"))
    )
    (net (code "29") (name "/GPA5") (class "Default")
      (node (ref "IC2") (pin "26") (pinfunction "GPA5_26") (pintype "bidirectional"))
      (node (ref "Q6") (pin "2") (pinfunction "S_2") (pintype "passive"))
      (node (ref "R75") (pin "1") (pinfunction "1_1") (pintype "passive"))
    )
    (net (code "30") (name "/GPA6") (class "Default")
      (node (ref "IC2") (pin "27") (pinfunction "GPA6_27") (pintype "bidirectional"))
      (node (ref "Q7") (pin "2") (pinfunction "S_2") (pintype "passive"))
      (node (ref "R77") (pin "1") (pinfunction "1_1") (pintype "passive"))
    )
    (net (code "31") (name "/GPA7") (class "Default")
      (node (ref "IC2") (pin "28") (pinfunction "GPA7_28") (pintype "bidirectional"))
      (node (ref "Q8") (pin "2") (pinfunction "S_2") (pintype "passive"))
      (node (ref "R79") (pin "1") (pinfunction "1_1") (pintype "passive"))
    )
    (net (code "32") (name "/GPB0") (class "Default")
      (node (ref "IC2") (pin "1") (pinfunction "GPB0_1") (pintype "bidirectional"))
      (node (ref "Q9") (pin "2") (pinfunction "S_2") (pintype "passive"))
      (node (ref "R81") (pin "1") (pinfunction "1_1") (pintype "passive"))
    )
    (net (code "33") (name "/GPB1") (class "Default")
      (node (ref "IC2") (pin "2") (pinfunction "GPB1_2") (pintype "bidirectional"))
      (node (ref "Q10") (pin "2") (pinfunction "S_2") (pintype "passive"))
      (node (ref "R101") (pin "1") (pinfunction "1_1") (pintype "passive"))
    )
    (net (code "34") (name "/GPB2") (class "Default")
      (node (ref "IC2") (pin "3") (pinfunction "GPB2_3") (pintype "bidirectional"))
      (node (ref "Q11") (pin "2") (pinfunction "S_2") (pintype "passive"))
      (node (ref "R103") (pin "1") (pinfunction "1_1") (pintype "passive"))
    )
    (net (code "35") (name "/GPB3") (class "Default")
      (node (ref "IC2") (pin "4") (pinfunction "GPB3_4") (pintype "bidirectional"))
      (node (ref "Q12") (pin "2") (pinfunction "S_2") (pintype "passive"))
      (node (ref "R105") (pin "1") (pinfunction "1_1") (pintype "passive"))
    )
    (net (code "36") (name "/GPB4") (class "Default")
      (node (ref "IC2") (pin "5") (pinfunction "GPB4_5") (pintype "bidirectional"))
      (node (ref "Q13") (pin "2") (pinfunction "S_2") (pintype "passive"))
      (node (ref "R107") (pin "1") (pinfunction "1_1") (pintype "passive"))
    )
    (net (code "37") (name "/GPB5") (class "Default")
      (node (ref "IC2") (pin "6") (pinfunction "GPB5_6") (pintype "bidirectional"))
      (node (ref "Q14") (pin "2") (pinfunction "S_2") (pintype "passive"))
      (node (ref "R109") (pin "1") (pinfunction "1_1") (pintype "passive"))
    )
    (net (code "38") (name "/GPB6") (class "Default")
      (node (ref "IC2") (pin "7") (pinfunction "GPB6_7") (pintype "bidirectional"))
      (node (ref "Q15") (pin "2") (pinfunction "S_2") (pintype "passive"))
      (node (ref "R111") (pin "1") (pinfunction "1_1") (pintype "passive"))
    )
    (net (code "39") (name "/GPB7") (class "Default")
      (node (ref "IC2") (pin "8") (pinfunction "GPB7_8") (pintype "bidirectional"))
      (node (ref "Q16") (pin "2") (pinfunction "S_2") (pintype "passive"))
      (node (ref "R113") (pin "1") (pinfunction "1_1") (pintype "passive"))
    )
    (net (code "40") (name "/INTA") (class "Default")
      (node (ref "6_INTA") (pin "1") (pinfunction "3_1") (pintype "passive"))
      (node (ref "IC2") (pin "20") (pinfunction "INTA_20") (pintype "output"))
      (node (ref "IC6") (pin "6-OUT1D") (pinfunction "6-OUT1D_6-OUT1D") (pintype "bidirectional"))
    )
    (net (code "41") (name "/INTB") (class "Default")
      (node (ref "7_INTB") (pin "1") (pinfunction "3_1") (pintype "passive"))
      (node (ref "IC2") (pin "19") (pinfunction "INTB_19") (pintype "output"))
      (node (ref "IC6") (pin "7-RX2/OUT1A") (pinfunction "7-RX2/OUT1A_7-RX2/OUT1A") (pintype "bidirectional"))
    )
    (net (code "42") (name "/OFFSET") (class "Default")
      (node (ref "OFFSET") (pin "1") (pinfunction "3_1") (pintype "passive"))
      (node (ref "R83") (pin "1") (pinfunction "1_1") (pintype "passive"))
      (node (ref "R84") (pin "1") (pinfunction "1_1") (pintype "passive"))
      (node (ref "R85") (pin "1") (pinfunction "1_1") (pintype "passive"))
      (node (ref "R86") (pin "1") (pinfunction "1_1") (pintype "passive"))
      (node (ref "R87") (pin "1") (pinfunction "1_1") (pintype "passive"))
      (node (ref "R88") (pin "1") (pinfunction "1_1") (pintype "passive"))
      (node (ref "R89") (pin "1") (pinfunction "1_1") (pintype "passive"))
      (node (ref "R90") (pin "1") (pinfunction "1_1") (pintype "passive"))
    )
    (net (code "43") (name "/SPI_CS_DAC1") (class "Default")
      (node (ref "9_DAC_CS") (pin "1") (pinfunction "3_1") (pintype "passive"))
      (node (ref "IC11") (pin "9") (pinfunction "~{SYNC}_9") (pintype "input"))
      (node (ref "IC6") (pin "9-OUT1C") (pinfunction "9-OUT1C_9-OUT1C") (pintype "bidirectional"))
    )
    (net (code "44") (name "/SPI_CS_DAC2") (class "Default")
      (node (ref "8_DAC_CS") (pin "1") (pinfunction "3_1") (pintype "passive"))
      (node (ref "IC10") (pin "9") (pinfunction "~{SYNC}_9") (pintype "input"))
      (node (ref "IC6") (pin "8-TX2/IN1") (pinfunction "8-TX2/IN1_8-TX2/IN1") (pintype "bidirectional"))
    )
    (net (code "45") (name "/SPI_IO_CS") (class "Default")
      (node (ref "10_IO_CS") (pin "1") (pinfunction "3_1") (pintype "passive"))
      (node (ref "IC2") (pin "11") (pinfunction "~{CS}_11") (pintype "input"))
      (node (ref "IC6") (pin "10-CS\\MQSR") (pinfunction "10-CS/MQSR_10-CS\\MQSR") (pintype "bidirectional"))
    )
    (net (code "46") (name "/SPI_MISO") (class "Default")
      (node (ref "12_MISO") (pin "1") (pinfunction "3_1") (pintype "passive"))
      (node (ref "IC2") (pin "14") (pinfunction "SO_14") (pintype "output"))
      (node (ref "IC6") (pin "12-MISO/MQSL") (pinfunction "12-MISO/MQSL_12-MISO/MQSL") (pintype "bidirectional"))
    )
    (net (code "47") (name "/SPI_MOSI") (class "Default")
      (node (ref "11_MOSI") (pin "1") (pinfunction "3_1") (pintype "passive"))
      (node (ref "IC10") (pin "11") (pinfunction "DIN_11") (pintype "input"))
      (node (ref "IC11") (pin "11") (pinfunction "DIN_11") (pintype "input"))
      (node (ref "IC2") (pin "13") (pinfunction "SI_13") (pintype "input"))
      (node (ref "IC6") (pin "11-MOSI/CTX1") (pinfunction "11-MOSI/CTX1_11-MOSI/CTX1") (pintype "bidirectional"))
    )
    (net (code "48") (name "/SPI_SCK") (class "Default")
      (node (ref "13_SCK") (pin "1") (pinfunction "3_1") (pintype "passive"))
      (node (ref "IC10") (pin "10") (pinfunction "SCLK_10") (pintype "input"))
      (node (ref "IC11") (pin "10") (pinfunction "SCLK_10") (pintype "input"))
      (node (ref "IC2") (pin "12") (pinfunction "SCK_12") (pintype "input"))
      (node (ref "IC6") (pin "13-SCK/LED") (pinfunction "13-SCK/LED_13-SCK/LED") (pintype "bidirectional"))
    )
    (net (code "49") (name "3.3V") (class "Default")
      (node (ref "3.3V") (pin "1") (pinfunction "3_1") (pintype "passive"))
      (node (ref "3.3V1") (pin "1") (pinfunction "3_1") (pintype "passive"))
      (node (ref "3.3V2") (pin "1") (pinfunction "3_1") (pintype "passive"))
      (node (ref "3.3V3") (pin "1") (pinfunction "3_1") (pintype "passive"))
      (node (ref "IC10") (pin "12") (pinfunction "IOVDD_12") (pintype "power_in"))
      (node (ref "IC11") (pin "12") (pinfunction "IOVDD_12") (pintype "power_in"))
      (node (ref "IC2") (pin "9") (pinfunction "VDD_9") (pintype "power_in"))
      (node (ref "IC6") (pin "3V3-3") (pinfunction "3V3-3_3V3-3") (pintype "bidirectional"))
      (node (ref "Q1") (pin "1") (pinfunction "G_1") (pintype "passive"))
      (node (ref "Q10") (pin "1") (pinfunction "G_1") (pintype "passive"))
      (node (ref "Q11") (pin "1") (pinfunction "G_1") (pintype "passive"))
      (node (ref "Q12") (pin "1") (pinfunction "G_1") (pintype "passive"))
      (node (ref "Q13") (pin "1") (pinfunction "G_1") (pintype "passive"))
      (node (ref "Q14") (pin "1") (pinfunction "G_1") (pintype "passive"))
      (node (ref "Q15") (pin "1") (pinfunction "G_1") (pintype "passive"))
      (node (ref "Q16") (pin "1") (pinfunction "G_1") (pintype "passive"))
      (node (ref "Q2") (pin "1") (pinfunction "G_1") (pintype "passive"))
      (node (ref "Q3") (pin "1") (pinfunction "G_1") (pintype "passive"))
      (node (ref "Q4") (pin "1") (pinfunction "G_1") (pintype "passive"))
      (node (ref "Q5") (pin "1") (pinfunction "G_1") (pintype "passive"))
      (node (ref "Q6") (pin "1") (pinfunction "G_1") (pintype "passive"))
      (node (ref "Q7") (pin "1") (pinfunction "G_1") (pintype "passive"))
      (node (ref "Q8") (pin "1") (pinfunction "G_1") (pintype "passive"))
      (node (ref "Q9") (pin "1") (pinfunction "G_1") (pintype "passive"))
      (node (ref "R101") (pin "2") (pinfunction "2_2") (pintype "passive"))
      (node (ref "R103") (pin "2") (pinfunction "2_2") (pintype "passive"))
      (node (ref "R105") (pin "2") (pinfunction "2_2") (pintype "passive"))
      (node (ref "R107") (pin "2") (pinfunction "2_2") (pintype "passive"))
      (node (ref "R109") (pin "2") (pinfunction "2_2") (pintype "passive"))
      (node (ref "R111") (pin "2") (pinfunction "2_2") (pintype "passive"))
      (node (ref "R113") (pin "2") (pinfunction "2_2") (pintype "passive"))
      (node (ref "R115") (pin "2") (pinfunction "2_2") (pintype "passive"))
      (node (ref "R116") (pin "2") (pinfunction "2_2") (pintype "passive"))
      (node (ref "R56") (pin "2") (pinfunction "2_2") (pintype "passive"))
      (node (ref "R57") (pin "2") (pinfunction "2_2") (pintype "passive"))
      (node (ref "R59") (pin "2") (pinfunction "2_2") (pintype "passive"))
      (node (ref "R61") (pin "2") (pinfunction "2_2") (pintype "passive"))
      (node (ref "R73") (pin "2") (pinfunction "2_2") (pintype "passive"))
      (node (ref "R75") (pin "2") (pinfunction "2_2") (pintype "passive"))
      (node (ref "R77") (pin "2") (pinfunction "2_2") (pintype "passive"))
      (node (ref "R79") (pin "2") (pinfunction "2_2") (pintype "passive"))
      (node (ref "R81") (pin "2") (pinfunction "2_2") (pintype "passive"))
      (node (ref "R82") (pin "1") (pinfunction "1_1") (pintype "passive"))
    )
    (net (code "50") (name "3.3V_A") (class "Default")
      (node (ref "3.3VA") (pin "1") (pinfunction "3_1") (pintype "passive"))
      (node (ref "3.3VA1") (pin "1") (pinfunction "3_1") (pintype "passive"))
      (node (ref "3.3VA2") (pin "1") (pinfunction "3_1") (pintype "passive"))
      (node (ref "3.3VA3") (pin "1") (pinfunction "3_1") (pintype "passive"))
      (node (ref "C15") (pin "2") (pinfunction "2_2") (pintype "passive"))
      (node (ref "C18") (pin "2") (pinfunction "2_2") (pintype "passive"))
      (node (ref "C30") (pin "+") (pinfunction "+_+") (pintype "passive"))
      (node (ref "C32") (pin "2") (pinfunction "2_2") (pintype "passive"))
      (node (ref "IC10") (pin "4") (pinfunction "AVDD_4") (pintype "power_in"))
      (node (ref "IC11") (pin "4") (pinfunction "AVDD_4") (pintype "power_in"))
      (node (ref "IC12") (pin "16") (pinfunction "VCC_16") (pintype "power_in"))
      (node (ref "IC3") (pin "4") (pinfunction "V+_4") (pintype "power_in"))
      (node (ref "IC4") (pin "4") (pinfunction "V+_4") (pintype "power_in"))
      (node (ref "IC9") (pin "1") (pinfunction "VOUT_1") (pintype "power_in"))
    )
    (net (code "51") (name "5V") (class "Default")
      (node (ref "5V") (pin "1") (pinfunction "3_1") (pintype "passive"))
      (node (ref "5V1") (pin "1") (pinfunction "3_1") (pintype "passive"))
      (node (ref "5V2") (pin "1") (pinfunction "3_1") (pintype "passive"))
      (node (ref "5V3") (pin "1") (pinfunction "3_1") (pintype "passive"))
      (node (ref "C27") (pin "2") (pinfunction "2_2") (pintype "passive"))
      (node (ref "C3") (pin "+") (pinfunction "+_+") (pintype "passive"))
      (node (ref "IC6") (pin "VIN") (pinfunction "VIN_VIN") (pintype "bidirectional"))
      (node (ref "IC7") (pin "3") (pinfunction "VO_3") (pintype "passive"))
      (node (ref "R100") (pin "2") (pinfunction "2_2") (pintype "passive"))
      (node (ref "R102") (pin "2") (pinfunction "2_2") (pintype "passive"))
      (node (ref "R104") (pin "2") (pinfunction "2_2") (pintype "passive"))
      (node (ref "R106") (pin "2") (pinfunction "2_2") (pintype "passive"))
      (node (ref "R108") (pin "2") (pinfunction "2_2") (pintype "passive"))
      (node (ref "R110") (pin "2") (pinfunction "2_2") (pintype "passive"))
      (node (ref "R112") (pin "2") (pinfunction "2_2") (pintype "passive"))
      (node (ref "R114") (pin "2") (pinfunction "2_2") (pintype "passive"))
      (node (ref "R58") (pin "2") (pinfunction "2_2") (pintype "passive"))
      (node (ref "R60") (pin "2") (pinfunction "2_2") (pintype "passive"))
      (node (ref "R72") (pin "2") (pinfunction "2_2") (pintype "passive"))
      (node (ref "R74") (pin "2") (pinfunction "2_2") (pintype "passive"))
      (node (ref "R76") (pin "2") (pinfunction "2_2") (pintype "passive"))
      (node (ref "R78") (pin "2") (pinfunction "2_2") (pintype "passive"))
      (node (ref "R80") (pin "2") (pinfunction "2_2") (pintype "passive"))
      (node (ref "R99") (pin "2") (pinfunction "2_2") (pintype "passive"))
    )
    (net (code "52") (name "GND") (class "Default")
      (node (ref "C1") (pin "-") (pinfunction "-_-") (pintype "passive"))
      (node (ref "C15") (pin "1") (pinfunction "1_1") (pintype "passive"))
      (node (ref "C18") (pin "1") (pinfunction "1_1") (pintype "passive"))
      (node (ref "C2") (pin "+") (pinfunction "+_+") (pintype "passive"))
      (node (ref "C23") (pin "1") (pinfunction "1_1") (pintype "passive"))
      (node (ref "C24") (pin "2") (pinfunction "2_2") (pintype "passive"))
      (node (ref "C25") (pin "2") (pinfunction "2_2") (pintype "passive"))
      (node (ref "C26") (pin "1") (pinfunction "1_1") (pintype "passive"))
      (node (ref "C27") (pin "1") (pinfunction "1_1") (pintype "passive"))
      (node (ref "C28") (pin "1") (pinfunction "1_1") (pintype "passive"))
      (node (ref "C29") (pin "1") (pinfunction "1_1") (pintype "passive"))
      (node (ref "C3") (pin "-") (pinfunction "-_-") (pintype "passive"))
      (node (ref "C30") (pin "-") (pinfunction "-_-") (pintype "passive"))
      (node (ref "C32") (pin "1") (pinfunction "1_1") (pintype "passive"))
      (node (ref "C33") (pin "2") (pinfunction "2_2") (pintype "passive"))
      (node (ref "C34") (pin "2") (pinfunction "2_2") (pintype "passive"))
      (node (ref "C6") (pin "1") (pinfunction "1_1") (pintype "passive"))
      (node (ref "GND") (pin "1") (pinfunction "3_1") (pintype "passive"))
      (node (ref "GND1") (pin "1") (pinfunction "3_1") (pintype "passive"))
      (node (ref "GND2") (pin "1") (pinfunction "3_1") (pintype "passive"))
      (node (ref "GND3") (pin "1") (pinfunction "3_1") (pintype "passive"))
      (node (ref "GND4") (pin "1") (pinfunction "3_1") (pintype "passive"))
      (node (ref "GND5") (pin "1") (pinfunction "3_1") (pintype "passive"))
      (node (ref "GND6") (pin "1") (pinfunction "3_1") (pintype "passive"))
      (node (ref "GND7") (pin "1") (pinfunction "3_1") (pintype "passive"))
      (node (ref "GND8") (pin "1") (pinfunction "3_1") (pintype "passive"))
      (node (ref "GND9") (pin "1") (pinfunction "3_1") (pintype "passive"))
      (node (ref "IC1") (pin "10") (pinfunction "+IN_10") (pintype "input"))
      (node (ref "IC1") (pin "12") (pinfunction "+IN_12") (pintype "input"))
      (node (ref "IC1") (pin "3") (pinfunction "+IN_3") (pintype "input"))
      (node (ref "IC1") (pin "5") (pinfunction "+IN_5") (pintype "input"))
      (node (ref "IC10") (pin "13") (pinfunction "A0_13") (pintype "input"))
      (node (ref "IC10") (pin "14") (pinfunction "A1_14") (pintype "input"))
      (node (ref "IC10") (pin "15") (pinfunction "~{ENABLE}_15") (pintype "input"))
      (node (ref "IC10") (pin "16") (pinfunction "LDAC_16") (pintype "input"))
      (node (ref "IC10") (pin "5") (pinfunction "VREFL_5") (pintype "input"))
      (node (ref "IC10") (pin "6") (pinfunction "GND_6") (pintype "power_in"))
      (node (ref "IC11") (pin "13") (pinfunction "A0_13") (pintype "input"))
      (node (ref "IC11") (pin "14") (pinfunction "A1_14") (pintype "input"))
      (node (ref "IC11") (pin "15") (pinfunction "~{ENABLE}_15") (pintype "input"))
      (node (ref "IC11") (pin "16") (pinfunction "LDAC_16") (pintype "input"))
      (node (ref "IC11") (pin "5") (pinfunction "VREFL_5") (pintype "input"))
      (node (ref "IC11") (pin "6") (pinfunction "GND_6") (pintype "power_in"))
      (node (ref "IC12") (pin "6") (pinfunction "~{E}_6") (pintype "input"))
      (node (ref "IC12") (pin "7") (pinfunction "VEE_7") (pintype "power_in"))
      (node (ref "IC12") (pin "8") (pinfunction "GND_8") (pintype "power_in"))
      (node (ref "IC2") (pin "10") (pinfunction "VSS_10") (pintype "power_in"))
      (node (ref "IC2") (pin "15") (pinfunction "A0_15") (pintype "input"))
      (node (ref "IC2") (pin "16") (pinfunction "A1_16") (pintype "input"))
      (node (ref "IC2") (pin "17") (pinfunction "A2_17") (pintype "input"))
      (node (ref "IC3") (pin "10") (pinfunction "+IN_10") (pintype "input"))
      (node (ref "IC3") (pin "11") (pinfunction "V-_11") (pintype "power_in"))
      (node (ref "IC3") (pin "12") (pinfunction "+IN_12") (pintype "input"))
      (node (ref "IC3") (pin "3") (pinfunction "+IN_3") (pintype "input"))
      (node (ref "IC3") (pin "5") (pinfunction "+IN_5") (pintype "input"))
      (node (ref "IC4") (pin "10") (pinfunction "+IN_10") (pintype "input"))
      (node (ref "IC4") (pin "11") (pinfunction "V-_11") (pintype "power_in"))
      (node (ref "IC4") (pin "12") (pinfunction "+IN_12") (pintype "input"))
      (node (ref "IC4") (pin "3") (pinfunction "+IN_3") (pintype "input"))
      (node (ref "IC4") (pin "5") (pinfunction "+IN_5") (pintype "input"))
      (node (ref "IC5") (pin "10") (pinfunction "+IN_10") (pintype "input"))
      (node (ref "IC5") (pin "12") (pinfunction "+IN_12") (pintype "input"))
      (node (ref "IC5") (pin "3") (pinfunction "+IN_3") (pintype "input"))
      (node (ref "IC5") (pin "5") (pinfunction "+IN_5") (pintype "input"))
      (node (ref "IC6") (pin "GND1") (pinfunction "GND1_GND1") (pintype "bidirectional"))
      (node (ref "IC6") (pin "GND3") (pinfunction "GND3_GND3") (pintype "bidirectional"))
      (node (ref "IC6") (pin "GND6") (pinfunction "GND6_GND6") (pintype "bidirectional"))
      (node (ref "IC7") (pin "2") (pinfunction "GND_2") (pintype "passive"))
      (node (ref "IC8") (pin "1") (pinfunction "C_1") (pintype "input"))
      (node (ref "IC9") (pin "2") (pinfunction "GND_2") (pintype "power_in"))
      (node (ref "IC9") (pin "2-2") (pinfunction "GND_2-2") (pintype "power_in"))
    )
    (net (code "53") (name "Net-(0_RX-3)") (class "Default")
      (node (ref "0_RX") (pin "1") (pinfunction "3_1") (pintype "passive"))
      (node (ref "IC6") (pin "0-RX1/CS1/CRX2") (pinfunction "0-RX1/CS1/CRX2_0-RX1/CS1/CRX2") (pintype "bidirectional"))
    )
    (net (code "54") (name "Net-(1_TX-3)") (class "Default")
      (node (ref "1_TX") (pin "1") (pinfunction "3_1") (pintype "passive"))
      (node (ref "IC6") (pin "1-TX1/MISO1/CTX2") (pinfunction "1-TX1/MISO1/CTX2_1-TX1/MISO1/CTX2") (pintype "bidirectional"))
    )
    (net (code "55") (name "Net-(5-3)") (class "Default")
      (node (ref "5") (pin "1") (pinfunction "3_1") (pintype "passive"))
      (node (ref "IC6") (pin "5-IN2") (pinfunction "5-IN2_5-IN2") (pintype "bidirectional"))
    )
    (net (code "56") (name "Net-(18_SDA-3)") (class "Default")
      (node (ref "18_SDA") (pin "1") (pinfunction "3_1") (pintype "passive"))
      (node (ref "IC6") (pin "18-A4/SDA0") (pinfunction "18-A4/SDA0_18-A4/SDA0") (pintype "bidirectional"))
      (node (ref "R115") (pin "1") (pinfunction "1_1") (pintype "passive"))
    )
    (net (code "57") (name "Net-(19_SCL-3)") (class "Default")
      (node (ref "19_SCL") (pin "1") (pinfunction "3_1") (pintype "passive"))
      (node (ref "IC6") (pin "19-A5/SCL0") (pinfunction "19-A5/SCL0_19-A5/SCL0") (pintype "bidirectional"))
      (node (ref "R116") (pin "1") (pinfunction "1_1") (pintype "passive"))
    )
    (net (code "58") (name "Net-(28-3)") (class "Default")
      (node (ref "28") (pin "1") (pinfunction "3_1") (pintype "passive"))
      (node (ref "IC6") (pin "28-RX7") (pinfunction "28-RX7_28-RX7") (pintype "bidirectional"))
    )
    (net (code "59") (name "Net-(29-3)") (class "Default")
      (node (ref "29") (pin "1") (pinfunction "3_1") (pintype "passive"))
      (node (ref "IC6") (pin "29-TX7") (pinfunction "29-TX7_29-TX7") (pintype "bidirectional"))
    )
    (net (code "60") (name "Net-(30-3)") (class "Default")
      (node (ref "30") (pin "1") (pinfunction "3_1") (pintype "passive"))
      (node (ref "IC6") (pin "30-CRX3") (pinfunction "30-CRX3_30-CRX3") (pintype "bidirectional"))
    )
    (net (code "61") (name "Net-(31-3)") (class "Default")
      (node (ref "31") (pin "1") (pinfunction "3_1") (pintype "passive"))
      (node (ref "IC6") (pin "31-CTX3") (pinfunction "31-CTX3_31-CTX3") (pintype "bidirectional"))
    )
    (net (code "62") (name "Net-(32-3)") (class "Default")
      (node (ref "32") (pin "1") (pinfunction "3_1") (pintype "passive"))
      (node (ref "IC6") (pin "32-OUT1B") (pinfunction "32-OUT1B_32-OUT1B") (pintype "bidirectional"))
    )
    (net (code "63") (name "Net-(33-3)") (class "Default")
      (node (ref "33") (pin "1") (pinfunction "3_1") (pintype "passive"))
      (node (ref "IC6") (pin "33-MCLK2") (pinfunction "33-MCLK2_33-MCLK2") (pintype "bidirectional"))
    )
    (net (code "64") (name "Net-(34-3)") (class "Default")
      (node (ref "34") (pin "1") (pinfunction "3_1") (pintype "passive"))
      (node (ref "IC6") (pin "34-RX8") (pinfunction "34-RX8_34-RX8") (pintype "bidirectional"))
    )
    (net (code "65") (name "Net-(35-3)") (class "Default")
      (node (ref "35") (pin "1") (pinfunction "3_1") (pintype "passive"))
      (node (ref "IC6") (pin "35-TX8") (pinfunction "35/TX8_35-TX8") (pintype "bidirectional"))
    )
    (net (code "66") (name "Net-(36-3)") (class "Default")
      (node (ref "36") (pin "1") (pinfunction "3_1") (pintype "passive"))
      (node (ref "IC6") (pin "36-PWM") (pinfunction "36-PWM_36-PWM") (pintype "bidirectional"))
    )
    (net (code "67") (name "Net-(37-3)") (class "Default")
      (node (ref "37") (pin "1") (pinfunction "3_1") (pintype "passive"))
      (node (ref "IC6") (pin "37-PWM") (pinfunction "37-PWM_37-PWM") (pintype "bidirectional"))
    )
    (net (code "68") (name "Net-(38-3)") (class "Default")
      (node (ref "38") (pin "1") (pinfunction "3_1") (pintype "passive"))
      (node (ref "IC6") (pin "38-A14/CS/IN1") (pinfunction "38-A14/CS/IN1_38-A14/CS/IN1") (pintype "bidirectional"))
    )
    (net (code "69") (name "Net-(39-3)") (class "Default")
      (node (ref "39") (pin "1") (pinfunction "3_1") (pintype "passive"))
      (node (ref "IC6") (pin "39-A15/CS/OUT1A") (pinfunction "39-A15/CS/OUT1A_39-A15/CS/OUT1A") (pintype "bidirectional"))
    )
    (net (code "70") (name "Net-(40-3)") (class "Default")
      (node (ref "40") (pin "1") (pinfunction "3_1") (pintype "passive"))
      (node (ref "IC6") (pin "40-A16/CS1") (pinfunction "40-A16/CS1_40-A16/CS1") (pintype "bidirectional"))
    )
    (net (code "71") (name "Net-(41-3)") (class "Default")
      (node (ref "41") (pin "1") (pinfunction "3_1") (pintype "passive"))
      (node (ref "IC6") (pin "41-A17/MISO1") (pinfunction "41-A17/MISO1_41-A17/MISO1") (pintype "bidirectional"))
    )
    (net (code "72") (name "Net-(CV1-3)") (class "Default")
      (node (ref "CV1") (pin "1") (pinfunction "3_1") (pintype "passive"))
      (node (ref "R31") (pin "1") (pinfunction "1_1") (pintype "passive"))
    )
    (net (code "73") (name "Net-(CV1B-3)") (class "Default")
      (node (ref "CV1B") (pin "1") (pinfunction "3_1") (pintype "passive"))
      (node (ref "R32") (pin "1") (pinfunction "1_1") (pintype "passive"))
    )
    (net (code "74") (name "Net-(CV2-3)") (class "Default")
      (node (ref "CV2") (pin "1") (pinfunction "3_1") (pintype "passive"))
      (node (ref "R27") (pin "1") (pinfunction "1_1") (pintype "passive"))
    )
    (net (code "75") (name "Net-(CV2B-3)") (class "Default")
      (node (ref "CV2B") (pin "1") (pinfunction "3_1") (pintype "passive"))
      (node (ref "R28") (pin "1") (pinfunction "1_1") (pintype "passive"))
    )
    (net (code "76") (name "Net-(CV3-3)") (class "Default")
      (node (ref "CV3") (pin "1") (pinfunction "3_1") (pintype "passive"))
      (node (ref "R22") (pin "1") (pinfunction "1_1") (pintype "passive"))
    )
    (net (code "77") (name "Net-(CV3B-3)") (class "Default")
      (node (ref "CV3B") (pin "1") (pinfunction "3_1") (pintype "passive"))
      (node (ref "R23") (pin "1") (pinfunction "1_1") (pintype "passive"))
    )
    (net (code "78") (name "Net-(CV4-3)") (class "Default")
      (node (ref "CV4") (pin "1") (pinfunction "3_1") (pintype "passive"))
      (node (ref "R35") (pin "1") (pinfunction "1_1") (pintype "passive"))
    )
    (net (code "79") (name "Net-(CV4B-3)") (class "Default")
      (node (ref "CV4B") (pin "1") (pinfunction "3_1") (pintype "passive"))
      (node (ref "R36") (pin "1") (pinfunction "1_1") (pintype "passive"))
    )
    (net (code "80") (name "Net-(CV5-3)") (class "Default")
      (node (ref "CV5") (pin "1") (pinfunction "3_1") (pintype "passive"))
      (node (ref "R65") (pin "1") (pinfunction "1_1") (pintype "passive"))
    )
    (net (code "81") (name "Net-(CV5B-3)") (class "Default")
      (node (ref "CV5B") (pin "1") (pinfunction "3_1") (pintype "passive"))
      (node (ref "R66") (pin "1") (pinfunction "1_1") (pintype "passive"))
    )
    (net (code "82") (name "Net-(CV6-3)") (class "Default")
      (node (ref "CV6") (pin "1") (pinfunction "3_1") (pintype "passive"))
      (node (ref "R62") (pin "1") (pinfunction "1_1") (pintype "passive"))
    )
    (net (code "83") (name "Net-(CV6B-3)") (class "Default")
      (node (ref "CV6B") (pin "1") (pinfunction "3_1") (pintype "passive"))
      (node (ref "R63") (pin "1") (pinfunction "1_1") (pintype "passive"))
    )
    (net (code "84") (name "Net-(CV7-3)") (class "Default")
      (node (ref "CV7") (pin "1") (pinfunction "3_1") (pintype "passive"))
      (node (ref "R11") (pin "1") (pinfunction "1_1") (pintype "passive"))
    )
    (net (code "85") (name "Net-(CV7B-3)") (class "Default")
      (node (ref "CV7B") (pin "1") (pinfunction "3_1") (pintype "passive"))
      (node (ref "R12") (pin "1") (pinfunction "1_1") (pintype "passive"))
    )
    (net (code "86") (name "Net-(CV8-3)") (class "Default")
      (node (ref "CV8") (pin "1") (pinfunction "3_1") (pintype "passive"))
      (node (ref "R69") (pin "1") (pinfunction "1_1") (pintype "passive"))
    )
    (net (code "87") (name "Net-(CV8B-3)") (class "Default")
      (node (ref "CV8B") (pin "1") (pinfunction "3_1") (pintype "passive"))
      (node (ref "R70") (pin "1") (pinfunction "1_1") (pintype "passive"))
    )
    (net (code "88") (name "Net-(CVO1-3)") (class "Default")
      (node (ref "CVO1") (pin "1") (pinfunction "3_1") (pintype "passive"))
      (node (ref "R47") (pin "2") (pinfunction "2_2") (pintype "passive"))
    )
    (net (code "89") (name "Net-(CVO2-3)") (class "Default")
      (node (ref "CVO2") (pin "1") (pinfunction "3_1") (pintype "passive"))
      (node (ref "R38") (pin "2") (pinfunction "2_2") (pintype "passive"))
    )
    (net (code "90") (name "Net-(CVO3-3)") (class "Default")
      (node (ref "CVO3") (pin "1") (pinfunction "3_1") (pintype "passive"))
      (node (ref "R41") (pin "2") (pinfunction "2_2") (pintype "passive"))
    )
    (net (code "91") (name "Net-(CVO4-3)") (class "Default")
      (node (ref "CVO4") (pin "1") (pinfunction "3_1") (pintype "passive"))
      (node (ref "R44") (pin "2") (pinfunction "2_2") (pintype "passive"))
    )
    (net (code "92") (name "Net-(CVO5-3)") (class "Default")
      (node (ref "CVO5") (pin "1") (pinfunction "3_1") (pintype "passive"))
      (node (ref "R18") (pin "2") (pinfunction "2_2") (pintype "passive"))
    )
    (net (code "93") (name "Net-(CVO6-3)") (class "Default")
      (node (ref "CVO6") (pin "1") (pinfunction "3_1") (pintype "passive"))
      (node (ref "R3") (pin "2") (pinfunction "2_2") (pintype "passive"))
    )
    (net (code "94") (name "Net-(CVO7-3)") (class "Default")
      (node (ref "CVO7") (pin "1") (pinfunction "3_1") (pintype "passive"))
      (node (ref "R6") (pin "2") (pinfunction "2_2") (pintype "passive"))
    )
    (net (code "95") (name "Net-(CVO8-3)") (class "Default")
      (node (ref "CVO8") (pin "1") (pinfunction "3_1") (pintype "passive"))
      (node (ref "R14") (pin "2") (pinfunction "2_2") (pintype "passive"))
    )
    (net (code "96") (name "Net-(ENC1-3)") (class "Default")
      (node (ref "ENC1") (pin "1") (pinfunction "3_1") (pintype "passive"))
      (node (ref "IC6") (pin "3-LRCLK2") (pinfunction "3-LRCLK2_3-LRCLK2") (pintype "bidirectional"))
    )
    (net (code "97") (name "Net-(ENC2-3)") (class "Default")
      (node (ref "ENC2") (pin "1") (pinfunction "3_1") (pintype "passive"))
      (node (ref "IC6") (pin "4-BCLK2") (pinfunction "4-BCLK2_4-BCLK2") (pintype "bidirectional"))
    )
    (net (code "98") (name "Net-(ENCBTN-3)") (class "Default")
      (node (ref "ENCBTN") (pin "1") (pinfunction "3_1") (pintype "passive"))
      (node (ref "IC6") (pin "2-OUT2") (pinfunction "2-OUT2_2-OUT2") (pintype "bidirectional"))
    )
    (net (code "99") (name "Net-(IC1A--IN)") (class "Default")
      (node (ref "C4") (pin "1") (pinfunction "1_1") (pintype "passive"))
      (node (ref "IC1") (pin "2") (pinfunction "-IN_2") (pintype "input"))
      (node (ref "R1") (pin "1") (pinfunction "1_1") (pintype "passive"))
      (node (ref "R2") (pin "2") (pinfunction "2_2") (pintype "passive"))
      (node (ref "R48") (pin "2") (pinfunction "2_2") (pintype "passive"))
      (node (ref "R83") (pin "2") (pinfunction "2_2") (pintype "passive"))
    )
    (net (code "100") (name "Net-(IC1A-OUT)") (class "Default")
      (node (ref "C4") (pin "2") (pinfunction "2_2") (pintype "passive"))
      (node (ref "IC1") (pin "1") (pinfunction "OUT_1") (pintype "output"))
      (node (ref "R1") (pin "2") (pinfunction "2_2") (pintype "passive"))
      (node (ref "R3") (pin "1") (pinfunction "1_1") (pintype "passive"))
    )
    (net (code "101") (name "Net-(IC1B--IN)") (class "Default")
      (node (ref "C5") (pin "1") (pinfunction "1_1") (pintype "passive"))
      (node (ref "IC1") (pin "6") (pinfunction "-IN_6") (pintype "input"))
      (node (ref "R4") (pin "1") (pinfunction "1_1") (pintype "passive"))
      (node (ref "R49") (pin "2") (pinfunction "2_2") (pintype "passive"))
      (node (ref "R5") (pin "2") (pinfunction "2_2") (pintype "passive"))
      (node (ref "R84") (pin "2") (pinfunction "2_2") (pintype "passive"))
    )
    (net (code "102") (name "Net-(IC1B-OUT)") (class "Default")
      (node (ref "C5") (pin "2") (pinfunction "2_2") (pintype "passive"))
      (node (ref "IC1") (pin "7") (pinfunction "OUT_7") (pintype "output"))
      (node (ref "R4") (pin "2") (pinfunction "2_2") (pintype "passive"))
      (node (ref "R6") (pin "1") (pinfunction "1_1") (pintype "passive"))
    )
    (net (code "103") (name "Net-(IC1C--IN)") (class "Default")
      (node (ref "C8") (pin "1") (pinfunction "1_1") (pintype "passive"))
      (node (ref "IC1") (pin "9") (pinfunction "-IN_9") (pintype "input"))
      (node (ref "R10") (pin "2") (pinfunction "2_2") (pintype "passive"))
      (node (ref "R50") (pin "2") (pinfunction "2_2") (pintype "passive"))
      (node (ref "R85") (pin "2") (pinfunction "2_2") (pintype "passive"))
      (node (ref "R9") (pin "1") (pinfunction "1_1") (pintype "passive"))
    )
    (net (code "104") (name "Net-(IC1C-OUT)") (class "Default")
      (node (ref "C8") (pin "2") (pinfunction "2_2") (pintype "passive"))
      (node (ref "IC1") (pin "8") (pinfunction "OUT_8") (pintype "output"))
      (node (ref "R14") (pin "1") (pinfunction "1_1") (pintype "passive"))
      (node (ref "R9") (pin "2") (pinfunction "2_2") (pintype "passive"))
    )
    (net (code "105") (name "Net-(IC1D--IN)") (class "Default")
      (node (ref "C9") (pin "1") (pinfunction "1_1") (pintype "passive"))
      (node (ref "IC1") (pin "13") (pinfunction "-IN_13") (pintype "input"))
      (node (ref "R16") (pin "1") (pinfunction "1_1") (pintype "passive"))
      (node (ref "R17") (pin "2") (pinfunction "2_2") (pintype "passive"))
      (node (ref "R51") (pin "2") (pinfunction "2_2") (pintype "passive"))
      (node (ref "R86") (pin "2") (pinfunction "2_2") (pintype "passive"))
    )
    (net (code "106") (name "Net-(IC1D-OUT)") (class "Default")
      (node (ref "C9") (pin "2") (pinfunction "2_2") (pintype "passive"))
      (node (ref "IC1") (pin "14") (pinfunction "OUT_14") (pintype "output"))
      (node (ref "R16") (pin "2") (pinfunction "2_2") (pintype "passive"))
      (node (ref "R18") (pin "1") (pinfunction "1_1") (pintype "passive"))
    )
    (net (code "107") (name "Net-(IC2-~{RESET})") (class "Default")
      (node (ref "IC2") (pin "18") (pinfunction "~{RESET}_18") (pintype "input"))
      (node (ref "R82") (pin "2") (pinfunction "2_2") (pintype "passive"))
    )
    (net (code "108") (name "Net-(IC3A--IN)") (class "Default")
      (node (ref "C7") (pin "1") (pinfunction "1_1") (pintype "passive"))
      (node (ref "IC3") (pin "2") (pinfunction "-IN_2") (pintype "input"))
      (node (ref "R11") (pin "2") (pinfunction "2_2") (pintype "passive"))
      (node (ref "R12") (pin "2") (pinfunction "2_2") (pintype "passive"))
      (node (ref "R13") (pin "2") (pinfunction "2_2") (pintype "passive"))
      (node (ref "R8") (pin "1") (pinfunction "1_1") (pintype "passive"))
    )
    (net (code "109") (name "Net-(IC3B--IN)") (class "Default")
      (node (ref "C10") (pin "1") (pinfunction "1_1") (pintype "passive"))
      (node (ref "IC3") (pin "6") (pinfunction "-IN_6") (pintype "input"))
      (node (ref "R15") (pin "1") (pinfunction "1_1") (pintype "passive"))
      (node (ref "R29") (pin "2") (pinfunction "2_2") (pintype "passive"))
      (node (ref "R62") (pin "2") (pinfunction "2_2") (pintype "passive"))
      (node (ref "R63") (pin "2") (pinfunction "2_2") (pintype "passive"))
    )
    (net (code "110") (name "Net-(IC3C--IN)") (class "Default")
      (node (ref "C11") (pin "1") (pinfunction "1_1") (pintype "passive"))
      (node (ref "IC3") (pin "9") (pinfunction "-IN_9") (pintype "input"))
      (node (ref "R64") (pin "1") (pinfunction "1_1") (pintype "passive"))
      (node (ref "R65") (pin "2") (pinfunction "2_2") (pintype "passive"))
      (node (ref "R66") (pin "2") (pinfunction "2_2") (pintype "passive"))
      (node (ref "R67") (pin "2") (pinfunction "2_2") (pintype "passive"))
    )
    (net (code "111") (name "Net-(IC3D--IN)") (class "Default")
      (node (ref "C14") (pin "1") (pinfunction "1_1") (pintype "passive"))
      (node (ref "IC3") (pin "13") (pinfunction "-IN_13") (pintype "input"))
      (node (ref "R68") (pin "1") (pinfunction "1_1") (pintype "passive"))
      (node (ref "R69") (pin "2") (pinfunction "2_2") (pintype "passive"))
      (node (ref "R70") (pin "2") (pinfunction "2_2") (pintype "passive"))
      (node (ref "R71") (pin "2") (pinfunction "2_2") (pintype "passive"))
    )
    (net (code "112") (name "Net-(IC4A--IN)") (class "Default")
      (node (ref "C16") (pin "1") (pinfunction "1_1") (pintype "passive"))
      (node (ref "IC4") (pin "2") (pinfunction "-IN_2") (pintype "input"))
      (node (ref "R21") (pin "1") (pinfunction "1_1") (pintype "passive"))
      (node (ref "R22") (pin "2") (pinfunction "2_2") (pintype "passive"))
      (node (ref "R23") (pin "2") (pinfunction "2_2") (pintype "passive"))
      (node (ref "R24") (pin "2") (pinfunction "2_2") (pintype "passive"))
    )
    (net (code "113") (name "Net-(IC4B--IN)") (class "Default")
      (node (ref "C17") (pin "1") (pinfunction "1_1") (pintype "passive"))
      (node (ref "IC4") (pin "6") (pinfunction "-IN_6") (pintype "input"))
      (node (ref "R25") (pin "1") (pinfunction "1_1") (pintype "passive"))
      (node (ref "R26") (pin "2") (pinfunction "2_2") (pintype "passive"))
      (node (ref "R27") (pin "2") (pinfunction "2_2") (pintype "passive"))
      (node (ref "R28") (pin "2") (pinfunction "2_2") (pintype "passive"))
    )
    (net (code "114") (name "Net-(IC4C--IN)") (class "Default")
      (node (ref "C20") (pin "1") (pinfunction "1_1") (pintype "passive"))
      (node (ref "IC4") (pin "9") (pinfunction "-IN_9") (pintype "input"))
      (node (ref "R30") (pin "1") (pinfunction "1_1") (pintype "passive"))
      (node (ref "R31") (pin "2") (pinfunction "2_2") (pintype "passive"))
      (node (ref "R32") (pin "2") (pinfunction "2_2") (pintype "passive"))
      (node (ref "R33") (pin "2") (pinfunction "2_2") (pintype "passive"))
    )
    (net (code "115") (name "Net-(IC4D--IN)") (class "Default")
      (node (ref "C21") (pin "1") (pinfunction "1_1") (pintype "passive"))
      (node (ref "IC4") (pin "13") (pinfunction "-IN_13") (pintype "input"))
      (node (ref "R34") (pin "1") (pinfunction "1_1") (pintype "passive"))
      (node (ref "R35") (pin "2") (pinfunction "2_2") (pintype "passive"))
      (node (ref "R36") (pin "2") (pinfunction "2_2") (pintype "passive"))
      (node (ref "R37") (pin "2") (pinfunction "2_2") (pintype "passive"))
    )
    (net (code "116") (name "Net-(IC5A--IN)") (class "Default")
      (node (ref "C12") (pin "1") (pinfunction "1_1") (pintype "passive"))
      (node (ref "IC5") (pin "2") (pinfunction "-IN_2") (pintype "input"))
      (node (ref "R19") (pin "1") (pinfunction "1_1") (pintype "passive"))
      (node (ref "R20") (pin "2") (pinfunction "2_2") (pintype "passive"))
      (node (ref "R52") (pin "2") (pinfunction "2_2") (pintype "passive"))
      (node (ref "R90") (pin "2") (pinfunction "2_2") (pintype "passive"))
    )
    (net (code "117") (name "Net-(IC5A-OUT)") (class "Default")
      (node (ref "C12") (pin "2") (pinfunction "2_2") (pintype "passive"))
      (node (ref "IC5") (pin "1") (pinfunction "OUT_1") (pintype "output"))
      (node (ref "R19") (pin "2") (pinfunction "2_2") (pintype "passive"))
      (node (ref "R38") (pin "1") (pinfunction "1_1") (pintype "passive"))
    )
    (net (code "118") (name "Net-(IC5B--IN)") (class "Default")
      (node (ref "C13") (pin "1") (pinfunction "1_1") (pintype "passive"))
      (node (ref "IC5") (pin "6") (pinfunction "-IN_6") (pintype "input"))
      (node (ref "R39") (pin "1") (pinfunction "1_1") (pintype "passive"))
      (node (ref "R40") (pin "2") (pinfunction "2_2") (pintype "passive"))
      (node (ref "R53") (pin "2") (pinfunction "2_2") (pintype "passive"))
      (node (ref "R89") (pin "2") (pinfunction "2_2") (pintype "passive"))
    )
    (net (code "119") (name "Net-(IC5B-OUT)") (class "Default")
      (node (ref "C13") (pin "2") (pinfunction "2_2") (pintype "passive"))
      (node (ref "IC5") (pin "7") (pinfunction "OUT_7") (pintype "output"))
      (node (ref "R39") (pin "2") (pinfunction "2_2") (pintype "passive"))
      (node (ref "R41") (pin "1") (pinfunction "1_1") (pintype "passive"))
    )
    (net (code "120") (name "Net-(IC5C--IN)") (class "Default")
      (node (ref "C19") (pin "1") (pinfunction "1_1") (pintype "passive"))
      (node (ref "IC5") (pin "9") (pinfunction "-IN_9") (pintype "input"))
      (node (ref "R42") (pin "1") (pinfunction "1_1") (pintype "passive"))
      (node (ref "R43") (pin "2") (pinfunction "2_2") (pintype "passive"))
      (node (ref "R54") (pin "2") (pinfunction "2_2") (pintype "passive"))
      (node (ref "R88") (pin "2") (pinfunction "2_2") (pintype "passive"))
    )
    (net (code "121") (name "Net-(IC5C-OUT)") (class "Default")
      (node (ref "C19") (pin "2") (pinfunction "2_2") (pintype "passive"))
      (node (ref "IC5") (pin "8") (pinfunction "OUT_8") (pintype "output"))
      (node (ref "R42") (pin "2") (pinfunction "2_2") (pintype "passive"))
      (node (ref "R44") (pin "1") (pinfunction "1_1") (pintype "passive"))
    )
    (net (code "122") (name "Net-(IC5D--IN)") (class "Default")
      (node (ref "C22") (pin "1") (pinfunction "1_1") (pintype "passive"))
      (node (ref "IC5") (pin "13") (pinfunction "-IN_13") (pintype "input"))
      (node (ref "R45") (pin "1") (pinfunction "1_1") (pintype "passive"))
      (node (ref "R46") (pin "2") (pinfunction "2_2") (pintype "passive"))
      (node (ref "R55") (pin "2") (pinfunction "2_2") (pintype "passive"))
      (node (ref "R87") (pin "2") (pinfunction "2_2") (pintype "passive"))
    )
    (net (code "123") (name "Net-(IC5D-OUT)") (class "Default")
      (node (ref "C22") (pin "2") (pinfunction "2_2") (pintype "passive"))
      (node (ref "IC5") (pin "14") (pinfunction "OUT_14") (pintype "output"))
      (node (ref "R45") (pin "2") (pinfunction "2_2") (pintype "passive"))
      (node (ref "R47") (pin "1") (pinfunction "1_1") (pintype "passive"))
    )
    (net (code "124") (name "Net-(IC7-VI)") (class "Default")
      (node (ref "C28") (pin "2") (pinfunction "2_2") (pintype "passive"))
      (node (ref "IC7") (pin "1") (pinfunction "VI_1") (pintype "input"))
      (node (ref "L1") (pin "2") (pinfunction "2_2") (pintype "passive"))
    )
    (net (code "125") (name "Net-(IC9-VIN)") (class "Default")
      (node (ref "C29") (pin "2") (pinfunction "2_2") (pintype "passive"))
      (node (ref "IC9") (pin "3") (pinfunction "VIN_3") (pintype "power_in"))
      (node (ref "L2") (pin "2") (pinfunction "2_2") (pintype "passive"))
    )
    (net (code "126") (name "Net-(IC10-VREFH{slash}VREFOUT)") (class "Default")
      (node (ref "C34") (pin "1") (pinfunction "1_1") (pintype "passive"))
      (node (ref "IC10") (pin "3") (pinfunction "VREFH/VREFOUT_3") (pintype "bidirectional"))
    )
    (net (code "127") (name "Net-(IC11-VREFH{slash}VREFOUT)") (class "Default")
      (node (ref "C33") (pin "1") (pinfunction "1_1") (pintype "passive"))
      (node (ref "IC11") (pin "3") (pinfunction "VREFH/VREFOUT_3") (pintype "bidirectional"))
    )
    (net (code "128") (name "Net-(IC12-Y0)") (class "Default")
      (node (ref "IC12") (pin "13") (pinfunction "Y0_13") (pintype "bidirectional"))
      (node (ref "PT2") (pin "1") (pinfunction "3_1") (pintype "passive"))
      (node (ref "R93") (pin "1") (pinfunction "1_1") (pintype "passive"))
    )
    (net (code "129") (name "Net-(IC12-Y1)") (class "Default")
      (node (ref "IC12") (pin "14") (pinfunction "Y1_14") (pintype "bidirectional"))
      (node (ref "PT3") (pin "1") (pinfunction "3_1") (pintype "passive"))
      (node (ref "R92") (pin "1") (pinfunction "1_1") (pintype "passive"))
    )
    (net (code "130") (name "Net-(IC12-Y2)") (class "Default")
      (node (ref "IC12") (pin "15") (pinfunction "Y2_15") (pintype "bidirectional"))
      (node (ref "PT4") (pin "1") (pinfunction "3_1") (pintype "passive"))
      (node (ref "R91") (pin "1") (pinfunction "1_1") (pintype "passive"))
    )
    (net (code "131") (name "Net-(IC12-Y3)") (class "Default")
      (node (ref "IC12") (pin "12") (pinfunction "Y3_12") (pintype "bidirectional"))
      (node (ref "PT1") (pin "1") (pinfunction "3_1") (pintype "passive"))
      (node (ref "R94") (pin "1") (pinfunction "1_1") (pintype "passive"))
    )
    (net (code "132") (name "Net-(IC12-Y4)") (class "Default")
      (node (ref "IC12") (pin "1") (pinfunction "Y4_1") (pintype "bidirectional"))
      (node (ref "PT5") (pin "1") (pinfunction "3_1") (pintype "passive"))
    )
    (net (code "133") (name "Net-(IC12-Y5)") (class "Default")
      (node (ref "IC12") (pin "5") (pinfunction "Y5_5") (pintype "bidirectional"))
      (node (ref "PT8") (pin "1") (pinfunction "3_1") (pintype "passive"))
    )
    (net (code "134") (name "Net-(IC12-Y6)") (class "Default")
      (node (ref "IC12") (pin "2") (pinfunction "Y6_2") (pintype "bidirectional"))
      (node (ref "PT6") (pin "1") (pinfunction "3_1") (pintype "passive"))
    )
    (net (code "135") (name "Net-(IC12-Y7)") (class "Default")
      (node (ref "IC12") (pin "4") (pinfunction "Y7_4") (pintype "bidirectional"))
      (node (ref "PT7") (pin "1") (pinfunction "3_1") (pintype "passive"))
    )
    (net (code "136") (name "Net-(IO1-3)") (class "Default")
      (node (ref "IO1") (pin "1") (pinfunction "3_1") (pintype "passive"))
      (node (ref "Q9") (pin "3") (pinfunction "D_3") (pintype "passive"))
      (node (ref "R100") (pin "1") (pinfunction "1_1") (pintype "passive"))
    )
    (net (code "137") (name "Net-(IO2-3)") (class "Default")
      (node (ref "IO2") (pin "1") (pinfunction "3_1") (pintype "passive"))
      (node (ref "Q10") (pin "3") (pinfunction "D_3") (pintype "passive"))
      (node (ref "R102") (pin "1") (pinfunction "1_1") (pintype "passive"))
    )
    (net (code "138") (name "Net-(IO3-3)") (class "Default")
      (node (ref "IO3") (pin "1") (pinfunction "3_1") (pintype "passive"))
      (node (ref "Q11") (pin "3") (pinfunction "D_3") (pintype "passive"))
      (node (ref "R104") (pin "1") (pinfunction "1_1") (pintype "passive"))
    )
    (net (code "139") (name "Net-(IO4-3)") (class "Default")
      (node (ref "IO4") (pin "1") (pinfunction "3_1") (pintype "passive"))
      (node (ref "Q12") (pin "3") (pinfunction "D_3") (pintype "passive"))
      (node (ref "R106") (pin "1") (pinfunction "1_1") (pintype "passive"))
    )
    (net (code "140") (name "Net-(IO5-3)") (class "Default")
      (node (ref "IO5") (pin "1") (pinfunction "3_1") (pintype "passive"))
      (node (ref "Q13") (pin "3") (pinfunction "D_3") (pintype "passive"))
      (node (ref "R108") (pin "1") (pinfunction "1_1") (pintype "passive"))
    )
    (net (code "141") (name "Net-(IO6-3)") (class "Default")
      (node (ref "IO6") (pin "1") (pinfunction "3_1") (pintype "passive"))
      (node (ref "Q14") (pin "3") (pinfunction "D_3") (pintype "passive"))
      (node (ref "R110") (pin "1") (pinfunction "1_1") (pintype "passive"))
    )
    (net (code "142") (name "Net-(IO7-3)") (class "Default")
      (node (ref "IO7") (pin "1") (pinfunction "3_1") (pintype "passive"))
      (node (ref "Q15") (pin "3") (pinfunction "D_3") (pintype "passive"))
      (node (ref "R112") (pin "1") (pinfunction "1_1") (pintype "passive"))
    )
    (net (code "143") (name "Net-(IO8-3)") (class "Default")
      (node (ref "IO8") (pin "1") (pinfunction "3_1") (pintype "passive"))
      (node (ref "Q16") (pin "3") (pinfunction "D_3") (pintype "passive"))
      (node (ref "R114") (pin "1") (pinfunction "1_1") (pintype "passive"))
    )
    (net (code "144") (name "Net-(IO9-3)") (class "Default")
      (node (ref "IO9") (pin "1") (pinfunction "3_1") (pintype "passive"))
      (node (ref "Q1") (pin "3") (pinfunction "D_3") (pintype "passive"))
      (node (ref "R99") (pin "1") (pinfunction "1_1") (pintype "passive"))
    )
    (net (code "145") (name "Net-(IO10-3)") (class "Default")
      (node (ref "IO10") (pin "1") (pinfunction "3_1") (pintype "passive"))
      (node (ref "Q2") (pin "3") (pinfunction "D_3") (pintype "passive"))
      (node (ref "R58") (pin "1") (pinfunction "1_1") (pintype "passive"))
    )
    (net (code "146") (name "Net-(IO11-3)") (class "Default")
      (node (ref "IO11") (pin "1") (pinfunction "3_1") (pintype "passive"))
      (node (ref "Q3") (pin "3") (pinfunction "D_3") (pintype "passive"))
      (node (ref "R60") (pin "1") (pinfunction "1_1") (pintype "passive"))
    )
    (net (code "147") (name "Net-(IO12-3)") (class "Default")
      (node (ref "IO12") (pin "1") (pinfunction "3_1") (pintype "passive"))
      (node (ref "Q4") (pin "3") (pinfunction "D_3") (pintype "passive"))
      (node (ref "R72") (pin "1") (pinfunction "1_1") (pintype "passive"))
    )
    (net (code "148") (name "Net-(IO13-3)") (class "Default")
      (node (ref "IO13") (pin "1") (pinfunction "3_1") (pintype "passive"))
      (node (ref "Q5") (pin "3") (pinfunction "D_3") (pintype "passive"))
      (node (ref "R74") (pin "1") (pinfunction "1_1") (pintype "passive"))
    )
    (net (code "149") (name "Net-(IO14-3)") (class "Default")
      (node (ref "IO14") (pin "1") (pinfunction "3_1") (pintype "passive"))
      (node (ref "Q6") (pin "3") (pinfunction "D_3") (pintype "passive"))
      (node (ref "R76") (pin "1") (pinfunction "1_1") (pintype "passive"))
    )
    (net (code "150") (name "Net-(IO15-3)") (class "Default")
      (node (ref "IO15") (pin "1") (pinfunction "3_1") (pintype "passive"))
      (node (ref "Q7") (pin "3") (pinfunction "D_3") (pintype "passive"))
      (node (ref "R78") (pin "1") (pinfunction "1_1") (pintype "passive"))
    )
    (net (code "151") (name "Net-(IO16-3)") (class "Default")
      (node (ref "IO16") (pin "1") (pinfunction "3_1") (pintype "passive"))
      (node (ref "Q8") (pin "3") (pinfunction "D_3") (pintype "passive"))
      (node (ref "R80") (pin "1") (pinfunction "1_1") (pintype "passive"))
    )
    (net (code "152") (name "unconnected-(IC6-Pad3V3-1)") (class "Default")
      (node (ref "IC6") (pin "3V3-1") (pinfunction "3V3-1_3V3-1") (pintype "bidirectional"))
    )
    (net (code "153") (name "unconnected-(P1-3-Pad1)") (class "Default")
      (node (ref "P1") (pin "1") (pinfunction "3_1") (pintype "passive"))
    )
    (net (code "154") (name "unconnected-(P2-3-Pad1)") (class "Default")
      (node (ref "P2") (pin "1") (pinfunction "3_1") (pintype "passive"))
    )
    (net (code "155") (name "unconnected-(P3-3-Pad1)") (class "Default")
      (node (ref "P3") (pin "1") (pinfunction "3_1") (pintype "passive"))
    )
    (net (code "156") (name "unconnected-(P4-3-Pad1)") (class "Default")
      (node (ref "P4") (pin "1") (pinfunction "3_1") (pintype "passive"))
    )
    (net (code "157") (name "unconnected-(P5-3-Pad1)") (class "Default")
      (node (ref "P5") (pin "1") (pinfunction "3_1") (pintype "passive"))
    )
    (net (code "158") (name "unconnected-(P6-3-Pad1)") (class "Default")
      (node (ref "P6") (pin "1") (pinfunction "3_1") (pintype "passive"))
    )
    (net (code "159") (name "unconnected-(P7-3-Pad1)") (class "Default")
      (node (ref "P7") (pin "1") (pinfunction "3_1") (pintype "passive"))
    )
    (net (code "160") (name "unconnected-(P8-3-Pad1)") (class "Default")
      (node (ref "P8") (pin "1") (pinfunction "3_1") (pintype "passive"))
    )
    (net (code "161") (name "unconnected-(P9-3-Pad1)") (class "Default")
      (node (ref "P9") (pin "1") (pinfunction "3_1") (pintype "passive"))
    )
    (net (code "162") (name "unconnected-(P10-3-Pad1)") (class "Default")
      (node (ref "P10") (pin "1") (pinfunction "3_1") (pintype "passive"))
    )
    (net (code "163") (name "unconnected-(P11-3-Pad1)") (class "Default")
      (node (ref "P11") (pin "1") (pinfunction "3_1") (pintype "passive"))
    )
    (net (code "164") (name "unconnected-(P12-3-Pad1)") (class "Default")
      (node (ref "P12") (pin "1") (pinfunction "3_1") (pintype "passive"))
    )
    (net (code "165") (name "unconnected-(P13-3-Pad1)") (class "Default")
      (node (ref "P13") (pin "1") (pinfunction "3_1") (pintype "passive"))
    )
    (net (code "166") (name "unconnected-(P14-3-Pad1)") (class "Default")
      (node (ref "P14") (pin "1") (pinfunction "3_1") (pintype "passive"))
    )
    (net (code "167") (name "unconnected-(P15-3-Pad1)") (class "Default")
      (node (ref "P15") (pin "1") (pinfunction "3_1") (pintype "passive"))
    )
    (net (code "168") (name "unconnected-(P16-3-Pad1)") (class "Default")
      (node (ref "P16") (pin "1") (pinfunction "3_1") (pintype "passive"))
    )
    (net (code "169") (name "unconnected-(P17-3-Pad1)") (class "Default")
      (node (ref "P17") (pin "1") (pinfunction "3_1") (pintype "passive"))
    )
    (net (code "170") (name "unconnected-(P18-3-Pad1)") (class "Default")
      (node (ref "P18") (pin "1") (pinfunction "3_1") (pintype "passive"))
    )
    (net (code "171") (name "unconnected-(P19-3-Pad1)") (class "Default")
      (node (ref "P19") (pin "1") (pinfunction "3_1") (pintype "passive"))
    )
    (net (code "172") (name "unconnected-(P21-3-Pad1)") (class "Default")
      (node (ref "P21") (pin "1") (pinfunction "3_1") (pintype "passive"))
    )
    (net (code "173") (name "unconnected-(P22-3-Pad1)") (class "Default")
      (node (ref "P22") (pin "1") (pinfunction "3_1") (pintype "passive"))
    )
    (net (code "174") (name "unconnected-(P23-3-Pad1)") (class "Default")
      (node (ref "P23") (pin "1") (pinfunction "3_1") (pintype "passive"))
    )
    (net (code "175") (name "unconnected-(P24-3-Pad1)") (class "Default")
      (node (ref "P24") (pin "1") (pinfunction "3_1") (pintype "passive"))
    )
    (net (code "176") (name "unconnected-(P25-3-Pad1)") (class "Default")
      (node (ref "P25") (pin "1") (pinfunction "3_1") (pintype "passive"))
    )
    (net (code "177") (name "unconnected-(P26-3-Pad1)") (class "Default")
      (node (ref "P26") (pin "1") (pinfunction "3_1") (pintype "passive"))
    )
    (net (code "178") (name "unconnected-(P27-3-Pad1)") (class "Default")
      (node (ref "P27") (pin "1") (pinfunction "3_1") (pintype "passive"))
    )
    (net (code "179") (name "unconnected-(P28-3-Pad1)") (class "Default")
      (node (ref "P28") (pin "1") (pinfunction "3_1") (pintype "passive"))
    )
    (net (code "180") (name "unconnected-(P29-3-Pad1)") (class "Default")
      (node (ref "P29") (pin "1") (pinfunction "3_1") (pintype "passive"))
    )
    (net (code "181") (name "unconnected-(P30-3-Pad1)") (class "Default")
      (node (ref "P30") (pin "1") (pinfunction "3_1") (pintype "passive"))
    )
    (net (code "182") (name "unconnected-(P31-3-Pad1)") (class "Default")
      (node (ref "P31") (pin "1") (pinfunction "3_1") (pintype "passive"))
    )
    (net (code "183") (name "unconnected-(P32-3-Pad1)") (class "Default")
      (node (ref "P32") (pin "1") (pinfunction "3_1") (pintype "passive"))
    )
    (net (code "184") (name "unconnected-(P33-3-Pad1)") (class "Default")
      (node (ref "P33") (pin "1") (pinfunction "3_1") (pintype "passive"))
    )
    (net (code "185") (name "unconnected-(P34-3-Pad1)") (class "Default")
      (node (ref "P34") (pin "1") (pinfunction "3_1") (pintype "passive"))
    )
    (net (code "186") (name "unconnected-(P35-3-Pad1)") (class "Default")
      (node (ref "P35") (pin "1") (pinfunction "3_1") (pintype "passive"))
    )
    (net (code "187") (name "unconnected-(P36-3-Pad1)") (class "Default")
      (node (ref "P36") (pin "1") (pinfunction "3_1") (pintype "passive"))
    )
    (net (code "188") (name "unconnected-(P37-3-Pad1)") (class "Default")
      (node (ref "P37") (pin "1") (pinfunction "3_1") (pintype "passive"))
    )
    (net (code "189") (name "unconnected-(P38-3-Pad1)") (class "Default")
      (node (ref "P38") (pin "1") (pinfunction "3_1") (pintype "passive"))
    )
    (net (code "190") (name "unconnected-(P39-3-Pad1)") (class "Default")
      (node (ref "P39") (pin "1") (pinfunction "3_1") (pintype "passive"))
    )
    (net (code "191") (name "unconnected-(P40-3-Pad1)") (class "Default")
      (node (ref "P40") (pin "1") (pinfunction "3_1") (pintype "passive"))
    )
    (net (code "192") (name "unconnected-(P41-3-Pad1)") (class "Default")
      (node (ref "P41") (pin "1") (pinfunction "3_1") (pintype "passive"))
    )
    (net (code "193") (name "unconnected-(P42-3-Pad1)") (class "Default")
      (node (ref "P42") (pin "1") (pinfunction "3_1") (pintype "passive"))
    )
    (net (code "194") (name "unconnected-(P44-3-Pad1)") (class "Default")
      (node (ref "P44") (pin "1") (pinfunction "3_1") (pintype "passive"))
    )
    (net (code "195") (name "unconnected-(P45-3-Pad1)") (class "Default")
      (node (ref "P45") (pin "1") (pinfunction "3_1") (pintype "passive"))
    )
    (net (code "196") (name "unconnected-(P46-3-Pad1)") (class "Default")
      (node (ref "P46") (pin "1") (pinfunction "3_1") (pintype "passive"))
    )
    (net (code "197") (name "unconnected-(P47-3-Pad1)") (class "Default")
      (node (ref "P47") (pin "1") (pinfunction "3_1") (pintype "passive"))
    )
    (net (code "198") (name "unconnected-(P49-3-Pad1)") (class "Default")
      (node (ref "P49") (pin "1") (pinfunction "3_1") (pintype "passive"))
    )
    (net (code "199") (name "unconnected-(P50-3-Pad1)") (class "Default")
      (node (ref "P50") (pin "1") (pinfunction "3_1") (pintype "passive"))
    )
  )
)
